# Radio_RPIv15_868.net
KiCad netlist of a schematic drawn in EAGLE
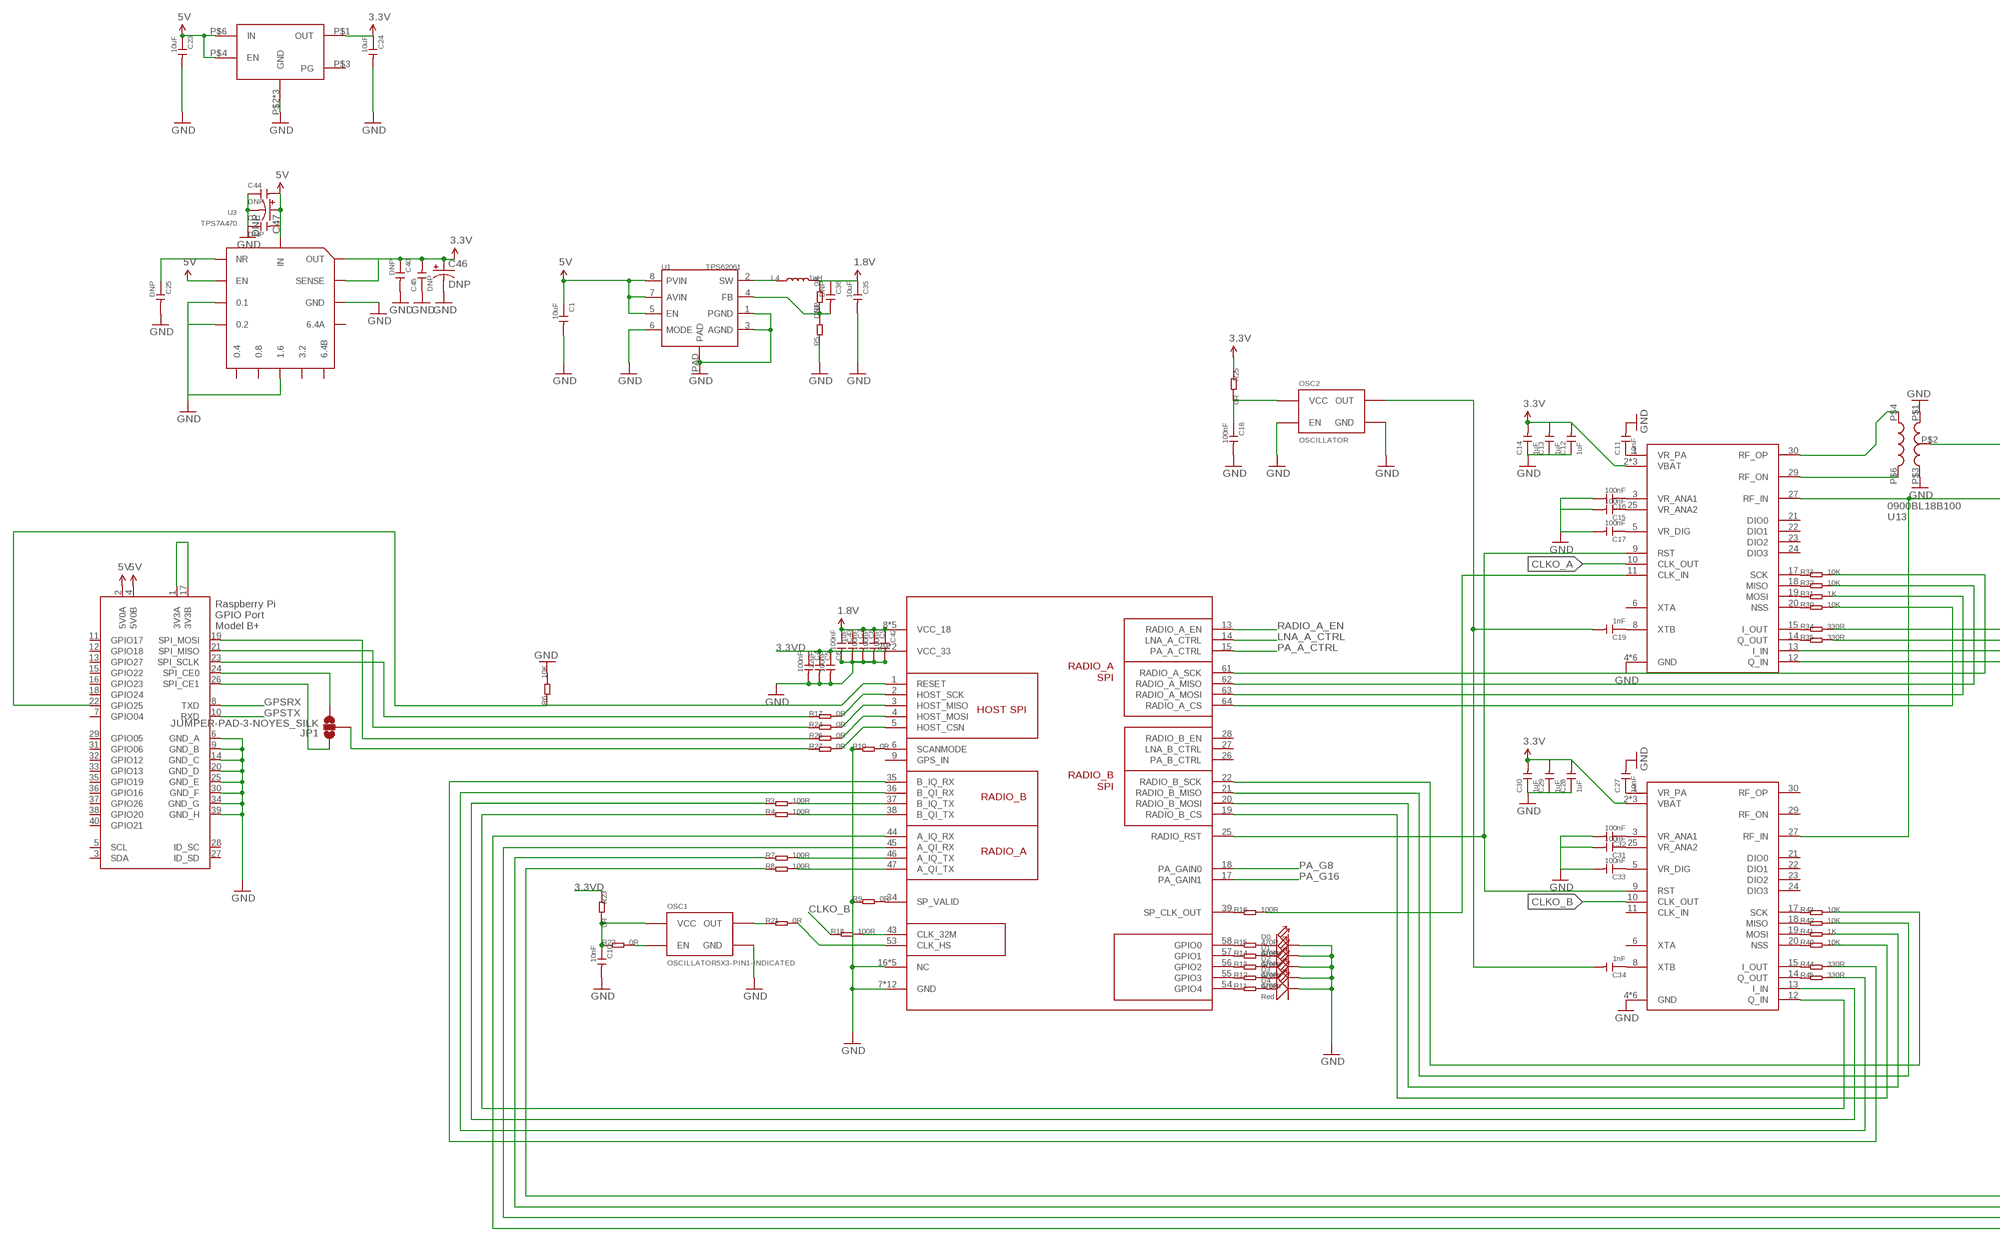
[diagram p0: schematic, sheet 1, part 1 of 2]
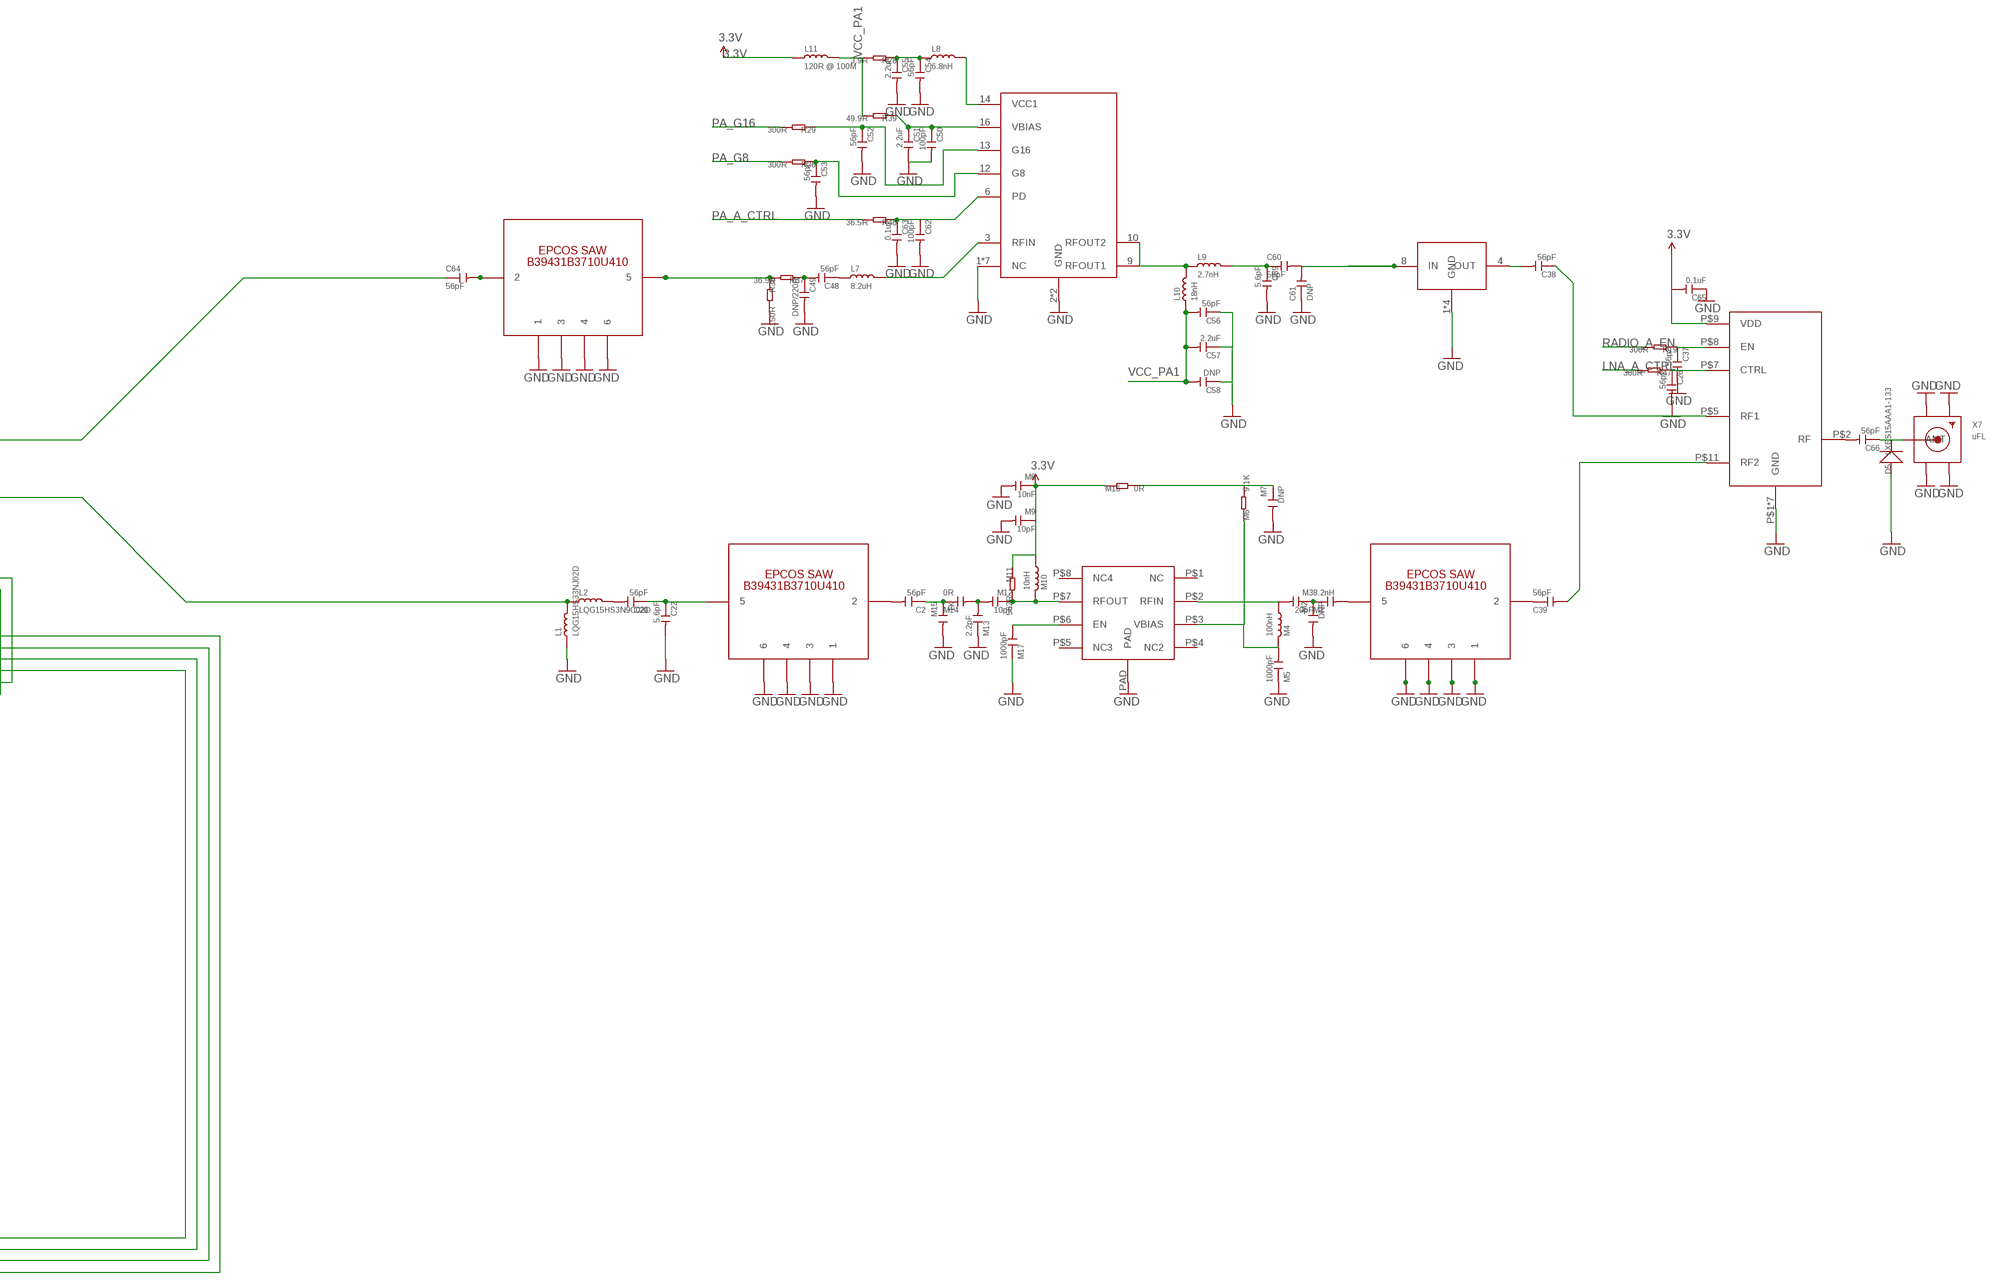
[diagram p1: schematic, sheet 1, part 2 of 2]

(export (version "E")
  (design (tool "Eeschema 10.0.6"))
  (components
    (comp (ref "C1")
      (value "10uF")
      (footprint "eagle-import:C0603@1")
      (libsource (lib "eagle-import") (part "CAP-0603"))
    )
    (comp (ref "C2")
      (value "56pF")
      (footprint "eagle-import:C0402@1")
      (libsource (lib "eagle-import") (part "CAP-0402"))
    )
    (comp (ref "C4")
      (value "100nF")
      (footprint "eagle-import:C0402@1")
      (libsource (lib "eagle-import") (part "CAP-0402"))
    )
    (comp (ref "C5")
      (value "22uF")
      (footprint "eagle-import:C0402@1")
      (libsource (lib "eagle-import") (part "CAP-0402"))
    )
    (comp (ref "C6")
      (value "100nF")
      (footprint "eagle-import:C0402@1")
      (libsource (lib "eagle-import") (part "CAP-0402"))
    )
    (comp (ref "C7")
      (value "1uF")
      (footprint "eagle-import:C0402@1")
      (libsource (lib "eagle-import") (part "CAP-0402"))
    )
    (comp (ref "C8")
      (value "100nF")
      (footprint "eagle-import:C0402@1")
      (libsource (lib "eagle-import") (part "CAP-0402"))
    )
    (comp (ref "C9")
      (value "100nF")
      (footprint "eagle-import:C0402@1")
      (libsource (lib "eagle-import") (part "CAP-0402"))
    )
    (comp (ref "C10")
      (value "10nF")
      (footprint "eagle-import:C0402@1")
      (libsource (lib "eagle-import") (part "CAP-0402"))
    )
    (comp (ref "C11")
      (value "10nF")
      (footprint "eagle-import:C0402@1")
      (libsource (lib "eagle-import") (part "CAP-0402"))
    )
    (comp (ref "C12")
      (value "1uF")
      (footprint "eagle-import:C0402@1")
      (libsource (lib "eagle-import") (part "CAP-0402"))
    )
    (comp (ref "C13")
      (value "1uF")
      (footprint "eagle-import:C0402@1")
      (libsource (lib "eagle-import") (part "CAP-0402"))
    )
    (comp (ref "C14")
      (value "1uF")
      (footprint "eagle-import:C0402@1")
      (libsource (lib "eagle-import") (part "CAP-0402"))
    )
    (comp (ref "C15")
      (value "100nF")
      (footprint "eagle-import:C0402@1")
      (libsource (lib "eagle-import") (part "CAP-0402"))
    )
    (comp (ref "C16")
      (value "100nF")
      (footprint "eagle-import:C0402@1")
      (libsource (lib "eagle-import") (part "CAP-0402"))
    )
    (comp (ref "C17")
      (value "100nF")
      (footprint "eagle-import:C0402@1")
      (libsource (lib "eagle-import") (part "CAP-0402"))
    )
    (comp (ref "C18")
      (value "100nF")
      (footprint "eagle-import:C0402@1")
      (libsource (lib "eagle-import") (part "CAP-0402"))
    )
    (comp (ref "C19")
      (value "1nF")
      (footprint "eagle-import:C0402@1")
      (libsource (lib "eagle-import") (part "CAP-0402"))
    )
    (comp (ref "C20")
      (value "56pF")
      (footprint "eagle-import:C0402@1")
      (libsource (lib "eagle-import") (part "CAP-0402"))
    )
    (comp (ref "C22")
      (value "5.6pF")
      (footprint "eagle-import:C0402@1")
      (libsource (lib "eagle-import") (part "CAP-0402"))
    )
    (comp (ref "C23")
      (value "10uF")
      (footprint "eagle-import:C0603@1")
      (libsource (lib "eagle-import") (part "CAP-0603"))
    )
    (comp (ref "C24")
      (value "10uF")
      (footprint "eagle-import:C0603@1")
      (libsource (lib "eagle-import") (part "CAP-0603"))
    )
    (comp (ref "C25")
      (value "DNP")
      (footprint "eagle-import:C0402@1")
      (libsource (lib "eagle-import") (part "CAP-0402"))
    )
    (comp (ref "C26")
      (value "56pF")
      (footprint "eagle-import:C0402@1")
      (libsource (lib "eagle-import") (part "CAP-0402"))
    )
    (comp (ref "C27")
      (value "10nF")
      (footprint "eagle-import:C0402@1")
      (libsource (lib "eagle-import") (part "CAP-0402"))
    )
    (comp (ref "C28")
      (value "1uF")
      (footprint "eagle-import:C0402@1")
      (libsource (lib "eagle-import") (part "CAP-0402"))
    )
    (comp (ref "C29")
      (value "1uF")
      (footprint "eagle-import:C0402@1")
      (libsource (lib "eagle-import") (part "CAP-0402"))
    )
    (comp (ref "C30")
      (value "1uF")
      (footprint "eagle-import:C0402@1")
      (libsource (lib "eagle-import") (part "CAP-0402"))
    )
    (comp (ref "C31")
      (value "100nF")
      (footprint "eagle-import:C0402@1")
      (libsource (lib "eagle-import") (part "CAP-0402"))
    )
    (comp (ref "C32")
      (value "100nF")
      (footprint "eagle-import:C0402@1")
      (libsource (lib "eagle-import") (part "CAP-0402"))
    )
    (comp (ref "C33")
      (value "100nF")
      (footprint "eagle-import:C0402@1")
      (libsource (lib "eagle-import") (part "CAP-0402"))
    )
    (comp (ref "C34")
      (value "1nF")
      (footprint "eagle-import:C0402@1")
      (libsource (lib "eagle-import") (part "CAP-0402"))
    )
    (comp (ref "C35")
      (value "10uF")
      (footprint "eagle-import:C0603@1")
      (libsource (lib "eagle-import") (part "CAP-0603"))
    )
    (comp (ref "C36")
      (value "DNP")
      (footprint "eagle-import:C0402@1")
      (libsource (lib "eagle-import") (part "CAP-0402"))
    )
    (comp (ref "C37")
      (value "56pF")
      (footprint "eagle-import:C0402@1")
      (libsource (lib "eagle-import") (part "CAP-0402"))
    )
    (comp (ref "C38")
      (value "56pF")
      (footprint "eagle-import:C0402@1")
      (libsource (lib "eagle-import") (part "CAP-0402"))
    )
    (comp (ref "C39")
      (value "56pF")
      (footprint "eagle-import:C0402@1")
      (libsource (lib "eagle-import") (part "CAP-0402"))
    )
    (comp (ref "C40")
      (value "DNP")
      (footprint "eagle-import:C0402@1")
      (libsource (lib "eagle-import") (part "CAP-0402"))
    )
    (comp (ref "C41")
      (value "DNP")
      (footprint "eagle-import:C0402@1")
      (libsource (lib "eagle-import") (part "CAP-0402"))
    )
    (comp (ref "C42")
      (value "100nF")
      (footprint "eagle-import:C0402@1")
      (libsource (lib "eagle-import") (part "CAP-0402"))
    )
    (comp (ref "C43")
      (value "100nF")
      (footprint "eagle-import:C0402@1")
      (libsource (lib "eagle-import") (part "CAP-0402"))
    )
    (comp (ref "C44")
      (value "DNP")
      (footprint "eagle-import:C0805@1")
      (libsource (lib "eagle-import") (part "CAP-0805"))
    )
    (comp (ref "C45")
      (value "DNP")
      (footprint "eagle-import:C0805@1")
      (libsource (lib "eagle-import") (part "CAP-0805"))
    )
    (comp (ref "C46")
      (value "DNP")
      (footprint "eagle-import:EIA3216")
      (libsource (lib "eagle-import") (part "CAP_POL1206"))
    )
    (comp (ref "C47")
      (value "DNP")
      (footprint "eagle-import:EIA3216")
      (libsource (lib "eagle-import") (part "CAP_POL1206"))
    )
    (comp (ref "C48")
      (value "56pF")
      (footprint "eagle-import:C0402@1")
      (libsource (lib "eagle-import") (part "CAP-0402"))
    )
    (comp (ref "C49")
      (value "DNP/220R")
      (footprint "eagle-import:C0402@1")
      (libsource (lib "eagle-import") (part "CAP-0402"))
    )
    (comp (ref "C50")
      (value "100pF")
      (footprint "eagle-import:C0402@1")
      (libsource (lib "eagle-import") (part "CAP-0402"))
    )
    (comp (ref "C51")
      (value "2.2uF")
      (footprint "eagle-import:C0402@1")
      (libsource (lib "eagle-import") (part "CAP-0402"))
    )
    (comp (ref "C52")
      (value "56pF")
      (footprint "eagle-import:C0402@1")
      (libsource (lib "eagle-import") (part "CAP-0402"))
    )
    (comp (ref "C53")
      (value "56pF")
      (footprint "eagle-import:C0402@1")
      (libsource (lib "eagle-import") (part "CAP-0402"))
    )
    (comp (ref "C54")
      (value "56pF")
      (footprint "eagle-import:C0402@1")
      (libsource (lib "eagle-import") (part "CAP-0402"))
    )
    (comp (ref "C55")
      (value "2.2uF")
      (footprint "eagle-import:C0402@1")
      (libsource (lib "eagle-import") (part "CAP-0402"))
    )
    (comp (ref "C56")
      (value "56pF")
      (footprint "eagle-import:C0402@1")
      (libsource (lib "eagle-import") (part "CAP-0402"))
    )
    (comp (ref "C57")
      (value "2.2uF")
      (footprint "eagle-import:C0402@1")
      (libsource (lib "eagle-import") (part "CAP-0402"))
    )
    (comp (ref "C58")
      (value "DNP")
      (footprint "eagle-import:C0402@1")
      (libsource (lib "eagle-import") (part "CAP-0402"))
    )
    (comp (ref "C59")
      (value "5.6pF")
      (footprint "eagle-import:C0402@1")
      (libsource (lib "eagle-import") (part "CAP-0402"))
    )
    (comp (ref "C60")
      (value "56pF")
      (footprint "eagle-import:C0402@1")
      (libsource (lib "eagle-import") (part "CAP-0402"))
    )
    (comp (ref "C61")
      (value "DNP")
      (footprint "eagle-import:C0402@1")
      (libsource (lib "eagle-import") (part "CAP-0402"))
    )
    (comp (ref "C62")
      (value "100pF")
      (footprint "eagle-import:C0402@1")
      (libsource (lib "eagle-import") (part "CAP-0402"))
    )
    (comp (ref "C63")
      (value "0.1uF")
      (footprint "eagle-import:C0402@1")
      (libsource (lib "eagle-import") (part "CAP-0402"))
    )
    (comp (ref "C64")
      (value "56pF")
      (footprint "eagle-import:C0402@1")
      (libsource (lib "eagle-import") (part "CAP-0402"))
    )
    (comp (ref "C65")
      (value "0.1uF")
      (footprint "eagle-import:C0402@1")
      (libsource (lib "eagle-import") (part "CAP-0402"))
    )
    (comp (ref "C66")
      (value "56pF")
      (footprint "eagle-import:C0402@1")
      (libsource (lib "eagle-import") (part "CAP-0402"))
    )
    (comp (ref "D0")
      (value "Green")
      (footprint "eagle-import:LED-0603")
      (libsource (lib "eagle-import") (part "LED-0603"))
    )
    (comp (ref "D1")
      (value "Green")
      (footprint "eagle-import:LED-0603")
      (libsource (lib "eagle-import") (part "LED-0603"))
    )
    (comp (ref "D2")
      (value "Green")
      (footprint "eagle-import:LED-0603")
      (libsource (lib "eagle-import") (part "LED-0603"))
    )
    (comp (ref "D3")
      (value "Green")
      (footprint "eagle-import:LED-0603")
      (libsource (lib "eagle-import") (part "LED-0603"))
    )
    (comp (ref "D4")
      (value "Red")
      (footprint "eagle-import:LED-0603")
      (libsource (lib "eagle-import") (part "LED-0603"))
    )
    (comp (ref "D5")
      (value "LXES15AAA1-133")
      (footprint "eagle-import:C0402")
      (libsource (lib "eagle-import") (part "D"))
    )
    (comp (ref "JP1")
      (value "JUMPER-PAD-3-NOYES_SILK")
      (footprint "eagle-import:PAD-JUMPER-3-NO_YES_SILK")
      (libsource (lib "eagle-import") (part "JUMPER-PAD-3-NOYES_SILK"))
    )
    (comp (ref "L1")
      (value "LQG15HS33NJ02D")
      (footprint "eagle-import:L0402@1")
      (libsource (lib "eagle-import") (part "INDUCTOR/FERRITE-BEAD-0402"))
    )
    (comp (ref "L2")
      (value "LQG15HS3N9C02D")
      (footprint "eagle-import:L0402@1")
      (libsource (lib "eagle-import") (part "INDUCTOR/FERRITE-BEAD-0402"))
    )
    (comp (ref "L4")
      (value "1uH")
      (footprint "eagle-import:1616BZ")
      (libsource (lib "eagle-import") (part "L'1616BZ'"))
    )
    (comp (ref "L7")
      (value "8.2uH")
      (footprint "eagle-import:L0402@1")
      (libsource (lib "eagle-import") (part "INDUCTOR/FERRITE-BEAD-0402"))
    )
    (comp (ref "L8")
      (value "6.8nH")
      (footprint "eagle-import:L0402@1")
      (libsource (lib "eagle-import") (part "INDUCTOR/FERRITE-BEAD-0402"))
    )
    (comp (ref "L9")
      (value "2.7nH")
      (footprint "eagle-import:L0402@1")
      (libsource (lib "eagle-import") (part "INDUCTOR/FERRITE-BEAD-0402"))
    )
    (comp (ref "L10")
      (value "18nH")
      (footprint "eagle-import:L0402@1")
      (libsource (lib "eagle-import") (part "INDUCTOR/FERRITE-BEAD-0402"))
    )
    (comp (ref "L11")
      (value "120R @ 100M")
      (footprint "eagle-import:L0402@1")
      (libsource (lib "eagle-import") (part "INDUCTOR/FERRITE-BEAD-0402"))
    )
    (comp (ref "M1")
      (value "8.2nH")
      (footprint "eagle-import:C0402@1")
      (libsource (lib "eagle-import") (part "CAP-0402"))
    )
    (comp (ref "M2")
      (value "DNP")
      (footprint "eagle-import:C0402@1")
      (libsource (lib "eagle-import") (part "CAP-0402"))
    )
    (comp (ref "M3")
      (value "20pF")
      (footprint "eagle-import:C0402@1")
      (libsource (lib "eagle-import") (part "CAP-0402"))
    )
    (comp (ref "M4")
      (value "100nH")
      (footprint "eagle-import:L0402@1")
      (libsource (lib "eagle-import") (part "INDUCTOR/FERRITE-BEAD-0402"))
    )
    (comp (ref "M5")
      (value "1000pF")
      (footprint "eagle-import:C0402@1")
      (libsource (lib "eagle-import") (part "CAP-0402"))
    )
    (comp (ref "M6")
      (value "9.1K")
      (footprint "eagle-import:R0402")
      (libsource (lib "eagle-import") (part "R-0402"))
    )
    (comp (ref "M7")
      (value "DNP")
      (footprint "eagle-import:C0402@1")
      (libsource (lib "eagle-import") (part "CAP-0402"))
    )
    (comp (ref "M8")
      (value "10nF")
      (footprint "eagle-import:C0402@1")
      (libsource (lib "eagle-import") (part "CAP-0402"))
    )
    (comp (ref "M9")
      (value "10pF")
      (footprint "eagle-import:C0402@1")
      (libsource (lib "eagle-import") (part "CAP-0402"))
    )
    (comp (ref "M10")
      (value "10nH")
      (footprint "eagle-import:L0402@1")
      (libsource (lib "eagle-import") (part "INDUCTOR/FERRITE-BEAD-0402"))
    )
    (comp (ref "M11")
      (value "562R")
      (footprint "eagle-import:R0402")
      (libsource (lib "eagle-import") (part "R-0402"))
    )
    (comp (ref "M12")
      (value "10pF")
      (footprint "eagle-import:C0402@1")
      (libsource (lib "eagle-import") (part "CAP-0402"))
    )
    (comp (ref "M13")
      (value "2.2pF")
      (footprint "eagle-import:C0402@1")
      (libsource (lib "eagle-import") (part "CAP-0402"))
    )
    (comp (ref "M14")
      (value "0R")
      (footprint "eagle-import:C0402@1")
      (libsource (lib "eagle-import") (part "CAP-0402"))
    )
    (comp (ref "M15")
      (value "1K")
      (footprint "eagle-import:C0402@1")
      (libsource (lib "eagle-import") (part "CAP-0402"))
    )
    (comp (ref "M16")
      (value "0R")
      (footprint "eagle-import:R0402")
      (libsource (lib "eagle-import") (part "R-0402"))
    )
    (comp (ref "M17")
      (value "1000pF")
      (footprint "eagle-import:C0402@1")
      (libsource (lib "eagle-import") (part "CAP-0402"))
    )
    (comp (ref "OSC1")
      (value "OSCILLATOR5X3-PIN1-INDICATED")
      (footprint "eagle-import:CRYSTAL-OSC-SMD-5X3")
      (libsource (lib "eagle-import") (part "OSCILLATOR5X3-PIN1-INDICATED"))
    )
    (comp (ref "OSC2")
      (value "OSCILLATOR")
      (footprint "eagle-import:CRYSTAL-OSC-SMD-3.2X2.5")
      (libsource (lib "eagle-import") (part "OSCILLATOR"))
    )
    (comp (ref "R1")
      (value "0R")
      (footprint "eagle-import:R0402")
      (libsource (lib "eagle-import") (part "R-0402"))
    )
    (comp (ref "R3")
      (value "100R")
      (footprint "eagle-import:R0402")
      (libsource (lib "eagle-import") (part "R-0402"))
    )
    (comp (ref "R4")
      (value "100R")
      (footprint "eagle-import:R0402")
      (libsource (lib "eagle-import") (part "R-0402"))
    )
    (comp (ref "R5")
      (value "DNP")
      (footprint "eagle-import:R0402")
      (libsource (lib "eagle-import") (part "R-0402"))
    )
    (comp (ref "R6")
      (value "10K")
      (footprint "eagle-import:R0402")
      (libsource (lib "eagle-import") (part "R-0402"))
    )
    (comp (ref "R7")
      (value "100R")
      (footprint "eagle-import:R0402")
      (libsource (lib "eagle-import") (part "R-0402"))
    )
    (comp (ref "R8")
      (value "100R")
      (footprint "eagle-import:R0402")
      (libsource (lib "eagle-import") (part "R-0402"))
    )
    (comp (ref "R9")
      (value "0R")
      (footprint "eagle-import:R0402")
      (libsource (lib "eagle-import") (part "R-0402"))
    )
    (comp (ref "R10")
      (value "0R")
      (footprint "eagle-import:R0402")
      (libsource (lib "eagle-import") (part "R-0402"))
    )
    (comp (ref "R11")
      (value "470R")
      (footprint "eagle-import:R0402")
      (libsource (lib "eagle-import") (part "R-0402"))
    )
    (comp (ref "R12")
      (value "470R")
      (footprint "eagle-import:R0402")
      (libsource (lib "eagle-import") (part "R-0402"))
    )
    (comp (ref "R13")
      (value "470R")
      (footprint "eagle-import:R0402")
      (libsource (lib "eagle-import") (part "R-0402"))
    )
    (comp (ref "R14")
      (value "470R")
      (footprint "eagle-import:R0402")
      (libsource (lib "eagle-import") (part "R-0402"))
    )
    (comp (ref "R15")
      (value "470R")
      (footprint "eagle-import:R0402")
      (libsource (lib "eagle-import") (part "R-0402"))
    )
    (comp (ref "R16")
      (value "100R")
      (footprint "eagle-import:R0402")
      (libsource (lib "eagle-import") (part "R-0402"))
    )
    (comp (ref "R17")
      (value "0R")
      (footprint "eagle-import:R0402")
      (libsource (lib "eagle-import") (part "R-0402"))
    )
    (comp (ref "R18")
      (value "100R")
      (footprint "eagle-import:R0402")
      (libsource (lib "eagle-import") (part "R-0402"))
    )
    (comp (ref "R19")
      (value "300R")
      (footprint "eagle-import:R0402")
      (libsource (lib "eagle-import") (part "R-0402"))
    )
    (comp (ref "R21")
      (value "0R")
      (footprint "eagle-import:R0402")
      (libsource (lib "eagle-import") (part "R-0402"))
    )
    (comp (ref "R22")
      (value "0R")
      (footprint "eagle-import:R0402")
      (libsource (lib "eagle-import") (part "R-0402"))
    )
    (comp (ref "R23")
      (value "0R")
      (footprint "eagle-import:R0402")
      (libsource (lib "eagle-import") (part "R-0402"))
    )
    (comp (ref "R24")
      (value "0R")
      (footprint "eagle-import:R0402")
      (libsource (lib "eagle-import") (part "R-0402"))
    )
    (comp (ref "R25")
      (value "0R")
      (footprint "eagle-import:R0402")
      (libsource (lib "eagle-import") (part "R-0402"))
    )
    (comp (ref "R26")
      (value "0R")
      (footprint "eagle-import:R0402")
      (libsource (lib "eagle-import") (part "R-0402"))
    )
    (comp (ref "R27")
      (value "0R")
      (footprint "eagle-import:R0402")
      (libsource (lib "eagle-import") (part "R-0402"))
    )
    (comp (ref "R28")
      (value "3.9R")
      (footprint "eagle-import:R0402")
      (libsource (lib "eagle-import") (part "R-0402"))
    )
    (comp (ref "R29")
      (value "300R")
      (footprint "eagle-import:R0402")
      (libsource (lib "eagle-import") (part "R-0402"))
    )
    (comp (ref "R30")
      (value "10K")
      (footprint "eagle-import:R0402")
      (libsource (lib "eagle-import") (part "R-0402"))
    )
    (comp (ref "R31")
      (value "1K")
      (footprint "eagle-import:R0402")
      (libsource (lib "eagle-import") (part "R-0402"))
    )
    (comp (ref "R32")
      (value "10K")
      (footprint "eagle-import:R0402")
      (libsource (lib "eagle-import") (part "R-0402"))
    )
    (comp (ref "R33")
      (value "10K")
      (footprint "eagle-import:R0402")
      (libsource (lib "eagle-import") (part "R-0402"))
    )
    (comp (ref "R34")
      (value "330R")
      (footprint "eagle-import:R0402")
      (libsource (lib "eagle-import") (part "R-0402"))
    )
    (comp (ref "R35")
      (value "330R")
      (footprint "eagle-import:R0402")
      (libsource (lib "eagle-import") (part "R-0402"))
    )
    (comp (ref "R36")
      (value "300R")
      (footprint "eagle-import:R0402")
      (libsource (lib "eagle-import") (part "R-0402"))
    )
    (comp (ref "R37")
      (value "36.5R")
      (footprint "eagle-import:R0402")
      (libsource (lib "eagle-import") (part "R-0402"))
    )
    (comp (ref "R38")
      (value "150R")
      (footprint "eagle-import:R0402")
      (libsource (lib "eagle-import") (part "R-0402"))
    )
    (comp (ref "R39")
      (value "49.9R")
      (footprint "eagle-import:R0402")
      (libsource (lib "eagle-import") (part "R-0402"))
    )
    (comp (ref "R40")
      (value "10K")
      (footprint "eagle-import:R0402")
      (libsource (lib "eagle-import") (part "R-0402"))
    )
    (comp (ref "R41")
      (value "1K")
      (footprint "eagle-import:R0402")
      (libsource (lib "eagle-import") (part "R-0402"))
    )
    (comp (ref "R42")
      (value "10K")
      (footprint "eagle-import:R0402")
      (libsource (lib "eagle-import") (part "R-0402"))
    )
    (comp (ref "R43")
      (value "10K")
      (footprint "eagle-import:R0402")
      (libsource (lib "eagle-import") (part "R-0402"))
    )
    (comp (ref "R44")
      (value "330R")
      (footprint "eagle-import:R0402")
      (libsource (lib "eagle-import") (part "R-0402"))
    )
    (comp (ref "R45")
      (value "330R")
      (footprint "eagle-import:R0402")
      (libsource (lib "eagle-import") (part "R-0402"))
    )
    (comp (ref "R46")
      (value "36.5R")
      (footprint "eagle-import:R0402")
      (libsource (lib "eagle-import") (part "R-0402"))
    )
    (comp (ref "R47")
      (value "300R")
      (footprint "eagle-import:R0402")
      (libsource (lib "eagle-import") (part "R-0402"))
    )
    (comp (ref "U$1")
      (value "SX1301")
      (footprint "eagle-import:QFN64G-0.5-9X9MM")
      (libsource (lib "eagle-import") (part "SX1301"))
    )
    (comp (ref "U$2")
      (value "SX1255")
      (footprint "eagle-import:QFN32G-0.5-5X5MM")
      (libsource (lib "eagle-import") (part "SX1255"))
    )
    (comp (ref "U$3")
      (value "SX1255")
      (footprint "eagle-import:QFN32G-0.5-5X5MM")
      (libsource (lib "eagle-import") (part "SX1255"))
    )
    (comp (ref "U$4")
      (value "B39921B3728U410")
      (footprint "eagle-import:EPCOS_SAW_FILTER")
      (libsource (lib "eagle-import") (part "EPCOS_SAW_FILTER"))
    )
    (comp (ref "U$5")
      (value "LP5912")
      (footprint "eagle-import:WSON6")
      (libsource (lib "eagle-import") (part "LP5912"))
    )
    (comp (ref "U$6")
      (value "0915LP15B026")
      (footprint "eagle-import:0915LP15B026")
      (libsource (lib "eagle-import") (part "0915LP15B026"))
    )
    (comp (ref "U$7")
      (value "RFSW1012")
      (footprint "eagle-import:QFN12-2X2MM")
      (libsource (lib "eagle-import") (part "RFSW1012"))
    )
    (comp (ref "U$8")
      (value "B39921B3728U410")
      (footprint "eagle-import:EPCOS_SAW_FILTER")
      (libsource (lib "eagle-import") (part "EPCOS_SAW_FILTER"))
    )
    (comp (ref "U$9")
      (value "EPCOS_SAW_FILTER")
      (footprint "eagle-import:EPCOS_SAW_FILTER")
      (libsource (lib "eagle-import") (part "EPCOS_SAW_FILTER"))
    )
    (comp (ref "U$10")
      (value "SKY67150_396LF")
      (footprint "eagle-import:8DFN")
      (libsource (lib "eagle-import") (part "SKY67150_396LF"))
    )
    (comp (ref "U1")
      (value "TPS62061")
      (footprint "eagle-import:WSON")
      (libsource (lib "eagle-import") (part "PMIC-ETA3410D2I-T(DFN8-2X2)WSON"))
    )
    (comp (ref "U3")
      (value "TPS7A470")
      (footprint "eagle-import:S-PVQFN-N20")
      (libsource (lib "eagle-import") (part "TPS7A470"))
    )
    (comp (ref "U6")
      (value "RFPA0133")
      (footprint "eagle-import:QFN16-3X3MM")
      (libsource (lib "eagle-import") (part "RFPA0133"))
    )
    (comp (ref "U13")
      (value "0900BL18B100")
      (footprint "eagle-import:BALUN_1206")
      (libsource (lib "eagle-import") (part "BALUN_1206"))
    )
    (comp (ref "X1")
      (value "RASPI_BOARD_B+#_H")
      (footprint "eagle-import:RASPI_BOARD_B+HAT")
      (libsource (lib "eagle-import") (part "RASPI_BOARD_B+#_H"))
    )
    (comp (ref "X7")
      (value "uFL")
      (footprint "eagle-import:SMA_EDGELAUNCH_UFL")
      (libsource (lib "eagle-import") (part "SMACONNECTOR_EDGE_UFL"))
    )
  )
  (nets
    (net (code "1") (name "/3.3VD") (class "Default")
      (node (ref "C4") (pin "1") (pinfunction "1_1") (pintype "passive"))
      (node (ref "C5") (pin "1") (pinfunction "1_1") (pintype "passive"))
      (node (ref "C6") (pin "1") (pinfunction "1_1") (pintype "passive"))
      (node (ref "R23") (pin "1") (pinfunction "1_1") (pintype "passive"))
      (node (ref "U$1") (pin "29") (pinfunction "VCC_33_29") (pintype "bidirectional"))
      (node (ref "U$1") (pin "52") (pinfunction "VCC_33_52") (pintype "bidirectional"))
    )
    (net (code "2") (name "/GPSRX") (class "Default")
      (node (ref "X1") (pin "8") (pinfunction "TXD_8") (pintype "bidirectional"))
    )
    (net (code "3") (name "/GPSTX") (class "Default")
      (node (ref "X1") (pin "10") (pinfunction "RXD_10") (pintype "bidirectional"))
    )
    (net (code "4") (name "/LNA_A_CTRL") (class "Default")
      (node (ref "R47") (pin "2") (pinfunction "2_2") (pintype "passive"))
      (node (ref "U$1") (pin "14") (pinfunction "LNA_A_CTRL_14") (pintype "bidirectional"))
    )
    (net (code "5") (name "/PA_A_CTRL") (class "Default")
      (node (ref "R46") (pin "2") (pinfunction "2_2") (pintype "passive"))
      (node (ref "U$1") (pin "15") (pinfunction "PA_A_CTRL_15") (pintype "bidirectional"))
    )
    (net (code "6") (name "/PA_G8") (class "Default")
      (node (ref "R36") (pin "2") (pinfunction "2_2") (pintype "passive"))
      (node (ref "U$1") (pin "18") (pinfunction "PA_GAIN0_18") (pintype "bidirectional"))
    )
    (net (code "7") (name "/PA_G16") (class "Default")
      (node (ref "R29") (pin "2") (pinfunction "2_2") (pintype "passive"))
      (node (ref "U$1") (pin "17") (pinfunction "PA_GAIN1_17") (pintype "bidirectional"))
    )
    (net (code "8") (name "/RADIO_A_EN") (class "Default")
      (node (ref "R19") (pin "2") (pinfunction "2_2") (pintype "passive"))
      (node (ref "U$1") (pin "13") (pinfunction "RADIO_A_EN_13") (pintype "bidirectional"))
    )
    (net (code "9") (name "/VCC_PA1") (class "Default")
      (node (ref "C56") (pin "2") (pinfunction "2_2") (pintype "passive"))
      (node (ref "C57") (pin "2") (pinfunction "2_2") (pintype "passive"))
      (node (ref "C58") (pin "2") (pinfunction "2_2") (pintype "passive"))
      (node (ref "L10") (pin "1") (pinfunction "1_1") (pintype "passive"))
      (node (ref "L11") (pin "2") (pinfunction "2_2") (pintype "passive"))
      (node (ref "R28") (pin "2") (pinfunction "2_2") (pintype "passive"))
      (node (ref "R39") (pin "2") (pinfunction "2_2") (pintype "passive"))
    )
    (net (code "10") (name "1.8V") (class "Default")
      (node (ref "C35") (pin "1") (pinfunction "1_1") (pintype "passive"))
      (node (ref "C36") (pin "1") (pinfunction "1_1") (pintype "passive"))
      (node (ref "C42") (pin "1") (pinfunction "1_1") (pintype "passive"))
      (node (ref "C43") (pin "1") (pinfunction "1_1") (pintype "passive"))
      (node (ref "C7") (pin "1") (pinfunction "1_1") (pintype "passive"))
      (node (ref "C8") (pin "1") (pinfunction "1_1") (pintype "passive"))
      (node (ref "C9") (pin "1") (pinfunction "1_1") (pintype "passive"))
      (node (ref "L4") (pin "2") (pinfunction "2_2") (pintype "passive"))
      (node (ref "R1") (pin "2") (pinfunction "2_2") (pintype "passive"))
      (node (ref "U$1") (pin "12") (pinfunction "VCC_18_12") (pintype "bidirectional"))
      (node (ref "U$1") (pin "23") (pinfunction "VCC_18_23") (pintype "bidirectional"))
      (node (ref "U$1") (pin "42") (pinfunction "VCC_18_42") (pintype "bidirectional"))
      (node (ref "U$1") (pin "60") (pinfunction "VCC_18_60") (pintype "bidirectional"))
      (node (ref "U$1") (pin "8") (pinfunction "VCC_18_8") (pintype "bidirectional"))
    )
    (net (code "11") (name "3.3V") (class "Default")
      (node (ref "C12") (pin "2") (pinfunction "2_2") (pintype "passive"))
      (node (ref "C13") (pin "2") (pinfunction "2_2") (pintype "passive"))
      (node (ref "C14") (pin "2") (pinfunction "2_2") (pintype "passive"))
      (node (ref "C24") (pin "1") (pinfunction "1_1") (pintype "passive"))
      (node (ref "C28") (pin "2") (pinfunction "2_2") (pintype "passive"))
      (node (ref "C29") (pin "2") (pinfunction "2_2") (pintype "passive"))
      (node (ref "C30") (pin "2") (pinfunction "2_2") (pintype "passive"))
      (node (ref "C40") (pin "1") (pinfunction "1_1") (pintype "passive"))
      (node (ref "C45") (pin "2") (pinfunction "2_2") (pintype "passive"))
      (node (ref "C46") (pin "A") (pinfunction "+_A") (pintype "passive"))
      (node (ref "C65") (pin "2") (pinfunction "2_2") (pintype "passive"))
      (node (ref "L11") (pin "1") (pinfunction "1_1") (pintype "passive"))
      (node (ref "M10") (pin "2") (pinfunction "2_2") (pintype "passive"))
      (node (ref "M11") (pin "1") (pinfunction "1_1") (pintype "passive"))
      (node (ref "M16") (pin "1") (pinfunction "1_1") (pintype "passive"))
      (node (ref "M8") (pin "1") (pinfunction "1_1") (pintype "passive"))
      (node (ref "M9") (pin "1") (pinfunction "1_1") (pintype "passive"))
      (node (ref "R25") (pin "1") (pinfunction "1_1") (pintype "passive"))
      (node (ref "U$2") (pin "16") (pinfunction "VBAT_16") (pintype "bidirectional"))
      (node (ref "U$2") (pin "2") (pinfunction "VBAT_2") (pintype "bidirectional"))
      (node (ref "U$2") (pin "32") (pinfunction "VBAT_32") (pintype "bidirectional"))
      (node (ref "U$3") (pin "16") (pinfunction "VBAT_16") (pintype "bidirectional"))
      (node (ref "U$3") (pin "2") (pinfunction "VBAT_2") (pintype "bidirectional"))
      (node (ref "U$3") (pin "32") (pinfunction "VBAT_32") (pintype "bidirectional"))
      (node (ref "U$5") (pin "P$1") (pinfunction "OUT_P$1") (pintype "bidirectional"))
      (node (ref "U$7") (pin "P$9") (pinfunction "VDD_P$9") (pintype "bidirectional"))
      (node (ref "U3") (pin "1") (pinfunction "OUT_1") (pintype "bidirectional"))
      (node (ref "U3") (pin "20") (pinfunction "OUT_20") (pintype "bidirectional"))
      (node (ref "U3") (pin "3") (pinfunction "SENSE_3") (pintype "bidirectional"))
    )
    (net (code "12") (name "5V") (class "Default")
      (node (ref "C1") (pin "1") (pinfunction "1_1") (pintype "passive"))
      (node (ref "C23") (pin "1") (pinfunction "1_1") (pintype "passive"))
      (node (ref "C41") (pin "2") (pinfunction "2_2") (pintype "passive"))
      (node (ref "C44") (pin "2") (pinfunction "2_2") (pintype "passive"))
      (node (ref "C47") (pin "A") (pinfunction "+_A") (pintype "passive"))
      (node (ref "U$5") (pin "P$4") (pinfunction "EN_P$4") (pintype "bidirectional"))
      (node (ref "U$5") (pin "P$6") (pinfunction "IN_P$6") (pintype "bidirectional"))
      (node (ref "U1") (pin "5") (pinfunction "EN_5") (pintype "bidirectional"))
      (node (ref "U1") (pin "7") (pinfunction "AVIN_7") (pintype "bidirectional"))
      (node (ref "U1") (pin "8") (pinfunction "PVIN_8") (pintype "bidirectional"))
      (node (ref "U3") (pin "13") (pinfunction "EN_13") (pintype "bidirectional"))
      (node (ref "U3") (pin "15") (pinfunction "IN_15") (pintype "bidirectional"))
      (node (ref "U3") (pin "16") (pinfunction "IN_16") (pintype "bidirectional"))
      (node (ref "X1") (pin "2") (pinfunction "5V0A_2") (pintype "power_in"))
      (node (ref "X1") (pin "4") (pinfunction "5V0B_4") (pintype "power_in"))
    )
    (net (code "13") (name "CLKO_A") (class "Default")
      (node (ref "U$2") (pin "10") (pinfunction "CLK_OUT_10") (pintype "bidirectional"))
    )
    (net (code "14") (name "CLKO_B") (class "Default")
      (node (ref "R18") (pin "1") (pinfunction "1_1") (pintype "passive"))
      (node (ref "U$3") (pin "10") (pinfunction "CLK_OUT_10") (pintype "bidirectional"))
    )
    (net (code "15") (name "GND") (class "Default")
      (node (ref "C1") (pin "2") (pinfunction "2_2") (pintype "passive"))
      (node (ref "C10") (pin "2") (pinfunction "2_2") (pintype "passive"))
      (node (ref "C11") (pin "2") (pinfunction "2_2") (pintype "passive"))
      (node (ref "C12") (pin "1") (pinfunction "1_1") (pintype "passive"))
      (node (ref "C13") (pin "1") (pinfunction "1_1") (pintype "passive"))
      (node (ref "C14") (pin "1") (pinfunction "1_1") (pintype "passive"))
      (node (ref "C15") (pin "2") (pinfunction "2_2") (pintype "passive"))
      (node (ref "C16") (pin "2") (pinfunction "2_2") (pintype "passive"))
      (node (ref "C17") (pin "2") (pinfunction "2_2") (pintype "passive"))
      (node (ref "C18") (pin "2") (pinfunction "2_2") (pintype "passive"))
      (node (ref "C22") (pin "2") (pinfunction "2_2") (pintype "passive"))
      (node (ref "C23") (pin "2") (pinfunction "2_2") (pintype "passive"))
      (node (ref "C24") (pin "2") (pinfunction "2_2") (pintype "passive"))
      (node (ref "C25") (pin "2") (pinfunction "2_2") (pintype "passive"))
      (node (ref "C26") (pin "2") (pinfunction "2_2") (pintype "passive"))
      (node (ref "C27") (pin "2") (pinfunction "2_2") (pintype "passive"))
      (node (ref "C28") (pin "1") (pinfunction "1_1") (pintype "passive"))
      (node (ref "C29") (pin "1") (pinfunction "1_1") (pintype "passive"))
      (node (ref "C30") (pin "1") (pinfunction "1_1") (pintype "passive"))
      (node (ref "C31") (pin "2") (pinfunction "2_2") (pintype "passive"))
      (node (ref "C32") (pin "2") (pinfunction "2_2") (pintype "passive"))
      (node (ref "C33") (pin "2") (pinfunction "2_2") (pintype "passive"))
      (node (ref "C35") (pin "2") (pinfunction "2_2") (pintype "passive"))
      (node (ref "C37") (pin "2") (pinfunction "2_2") (pintype "passive"))
      (node (ref "C4") (pin "2") (pinfunction "2_2") (pintype "passive"))
      (node (ref "C40") (pin "2") (pinfunction "2_2") (pintype "passive"))
      (node (ref "C41") (pin "1") (pinfunction "1_1") (pintype "passive"))
      (node (ref "C42") (pin "2") (pinfunction "2_2") (pintype "passive"))
      (node (ref "C43") (pin "2") (pinfunction "2_2") (pintype "passive"))
      (node (ref "C44") (pin "1") (pinfunction "1_1") (pintype "passive"))
      (node (ref "C45") (pin "1") (pinfunction "1_1") (pintype "passive"))
      (node (ref "C46") (pin "C") (pinfunction "-_C") (pintype "passive"))
      (node (ref "C47") (pin "C") (pinfunction "-_C") (pintype "passive"))
      (node (ref "C49") (pin "2") (pinfunction "2_2") (pintype "passive"))
      (node (ref "C5") (pin "2") (pinfunction "2_2") (pintype "passive"))
      (node (ref "C50") (pin "2") (pinfunction "2_2") (pintype "passive"))
      (node (ref "C51") (pin "2") (pinfunction "2_2") (pintype "passive"))
      (node (ref "C52") (pin "2") (pinfunction "2_2") (pintype "passive"))
      (node (ref "C53") (pin "2") (pinfunction "2_2") (pintype "passive"))
      (node (ref "C54") (pin "2") (pinfunction "2_2") (pintype "passive"))
      (node (ref "C55") (pin "2") (pinfunction "2_2") (pintype "passive"))
      (node (ref "C56") (pin "1") (pinfunction "1_1") (pintype "passive"))
      (node (ref "C57") (pin "1") (pinfunction "1_1") (pintype "passive"))
      (node (ref "C58") (pin "1") (pinfunction "1_1") (pintype "passive"))
      (node (ref "C59") (pin "2") (pinfunction "2_2") (pintype "passive"))
      (node (ref "C6") (pin "2") (pinfunction "2_2") (pintype "passive"))
      (node (ref "C61") (pin "1") (pinfunction "1_1") (pintype "passive"))
      (node (ref "C62") (pin "2") (pinfunction "2_2") (pintype "passive"))
      (node (ref "C63") (pin "2") (pinfunction "2_2") (pintype "passive"))
      (node (ref "C65") (pin "1") (pinfunction "1_1") (pintype "passive"))
      (node (ref "C7") (pin "2") (pinfunction "2_2") (pintype "passive"))
      (node (ref "C8") (pin "2") (pinfunction "2_2") (pintype "passive"))
      (node (ref "C9") (pin "2") (pinfunction "2_2") (pintype "passive"))
      (node (ref "D0") (pin "-") (pinfunction "-_-") (pintype "passive"))
      (node (ref "D1") (pin "-") (pinfunction "-_-") (pintype "passive"))
      (node (ref "D2") (pin "-") (pinfunction "-_-") (pintype "passive"))
      (node (ref "D3") (pin "-") (pinfunction "-_-") (pintype "passive"))
      (node (ref "D4") (pin "-") (pinfunction "-_-") (pintype "passive"))
      (node (ref "D5") (pin "1") (pinfunction "+_1") (pintype "passive"))
      (node (ref "L1") (pin "1") (pinfunction "1_1") (pintype "passive"))
      (node (ref "M13") (pin "1") (pinfunction "1_1") (pintype "passive"))
      (node (ref "M15") (pin "2") (pinfunction "2_2") (pintype "passive"))
      (node (ref "M17") (pin "1") (pinfunction "1_1") (pintype "passive"))
      (node (ref "M2") (pin "2") (pinfunction "2_2") (pintype "passive"))
      (node (ref "M5") (pin "1") (pinfunction "1_1") (pintype "passive"))
      (node (ref "M7") (pin "2") (pinfunction "2_2") (pintype "passive"))
      (node (ref "M8") (pin "2") (pinfunction "2_2") (pintype "passive"))
      (node (ref "M9") (pin "2") (pinfunction "2_2") (pintype "passive"))
      (node (ref "OSC1") (pin "2") (pinfunction "GND_2") (pintype "bidirectional"))
      (node (ref "OSC2") (pin "P$1") (pinfunction "EN_P$1") (pintype "bidirectional"))
      (node (ref "OSC2") (pin "P$2") (pinfunction "GND_P$2") (pintype "bidirectional"))
      (node (ref "R10") (pin "1") (pinfunction "1_1") (pintype "passive"))
      (node (ref "R38") (pin "2") (pinfunction "2_2") (pintype "passive"))
      (node (ref "R5") (pin "1") (pinfunction "1_1") (pintype "passive"))
      (node (ref "R6") (pin "2") (pinfunction "2_2") (pintype "passive"))
      (node (ref "R9") (pin "1") (pinfunction "1_1") (pintype "passive"))
      (node (ref "U$1") (pin "10") (pinfunction "GND_10") (pintype "bidirectional"))
      (node (ref "U$1") (pin "11") (pinfunction "GND_11") (pintype "bidirectional"))
      (node (ref "U$1") (pin "16") (pinfunction "NC_16") (pintype "bidirectional"))
      (node (ref "U$1") (pin "24") (pinfunction "GND_24") (pintype "bidirectional"))
      (node (ref "U$1") (pin "30") (pinfunction "GND_30") (pintype "bidirectional"))
      (node (ref "U$1") (pin "31") (pinfunction "GND_31") (pintype "bidirectional"))
      (node (ref "U$1") (pin "32") (pinfunction "NC_32") (pintype "bidirectional"))
      (node (ref "U$1") (pin "33") (pinfunction "NC_33") (pintype "bidirectional"))
      (node (ref "U$1") (pin "40") (pinfunction "GND_40") (pintype "bidirectional"))
      (node (ref "U$1") (pin "41") (pinfunction "GND_41") (pintype "bidirectional"))
      (node (ref "U$1") (pin "48") (pinfunction "NC_48") (pintype "bidirectional"))
      (node (ref "U$1") (pin "49") (pinfunction "NC_49") (pintype "bidirectional"))
      (node (ref "U$1") (pin "50") (pinfunction "GND_50") (pintype "bidirectional"))
      (node (ref "U$1") (pin "51") (pinfunction "GND_51") (pintype "bidirectional"))
      (node (ref "U$1") (pin "59") (pinfunction "GND_59") (pintype "bidirectional"))
      (node (ref "U$1") (pin "65") (pinfunction "GND_65") (pintype "bidirectional"))
      (node (ref "U$1") (pin "7") (pinfunction "GND_7") (pintype "bidirectional"))
      (node (ref "U$10") (pin "PAD") (pinfunction "PAD_PAD") (pintype "bidirectional"))
      (node (ref "U$2") (pin "26") (pinfunction "GND_26") (pintype "bidirectional"))
      (node (ref "U$2") (pin "28") (pinfunction "GND_28") (pintype "bidirectional"))
      (node (ref "U$2") (pin "31") (pinfunction "GND_31") (pintype "bidirectional"))
      (node (ref "U$2") (pin "33") (pinfunction "GND_33") (pintype "bidirectional"))
      (node (ref "U$2") (pin "4") (pinfunction "GND_4") (pintype "bidirectional"))
      (node (ref "U$2") (pin "7") (pinfunction "GND_7") (pintype "bidirectional"))
      (node (ref "U$3") (pin "26") (pinfunction "GND_26") (pintype "bidirectional"))
      (node (ref "U$3") (pin "28") (pinfunction "GND_28") (pintype "bidirectional"))
      (node (ref "U$3") (pin "31") (pinfunction "GND_31") (pintype "bidirectional"))
      (node (ref "U$3") (pin "33") (pinfunction "GND_33") (pintype "bidirectional"))
      (node (ref "U$3") (pin "4") (pinfunction "GND_4") (pintype "bidirectional"))
      (node (ref "U$3") (pin "7") (pinfunction "GND_7") (pintype "bidirectional"))
      (node (ref "U$4") (pin "P$1") (pinfunction "1_P$1") (pintype "bidirectional"))
      (node (ref "U$4") (pin "P$3") (pinfunction "3_P$3") (pintype "bidirectional"))
      (node (ref "U$4") (pin "P$4") (pinfunction "4_P$4") (pintype "bidirectional"))
      (node (ref "U$4") (pin "P$6") (pinfunction "6_P$6") (pintype "bidirectional"))
      (node (ref "U$5") (pin "P$2") (pinfunction "GND_P$2") (pintype "bidirectional"))
      (node (ref "U$5") (pin "P$5") (pinfunction "GND_P$5") (pintype "bidirectional"))
      (node (ref "U$5") (pin "PAD") (pinfunction "GND_PAD") (pintype "bidirectional"))
      (node (ref "U$6") (pin "1") (pinfunction "GND_1") (pintype "bidirectional"))
      (node (ref "U$6") (pin "3") (pinfunction "GND_3") (pintype "bidirectional"))
      (node (ref "U$6") (pin "5") (pinfunction "GND_5") (pintype "bidirectional"))
      (node (ref "U$6") (pin "7") (pinfunction "GND_7") (pintype "bidirectional"))
      (node (ref "U$7") (pin "P$1") (pinfunction "GND_P$1") (pintype "bidirectional"))
      (node (ref "U$7") (pin "P$10") (pinfunction "GND_P$10") (pintype "bidirectional"))
      (node (ref "U$7") (pin "P$12") (pinfunction "GND_P$12") (pintype "bidirectional"))
      (node (ref "U$7") (pin "P$3") (pinfunction "GND_P$3") (pintype "bidirectional"))
      (node (ref "U$7") (pin "P$4") (pinfunction "GND_P$4") (pintype "bidirectional"))
      (node (ref "U$7") (pin "P$6") (pinfunction "GND_P$6") (pintype "bidirectional"))
      (node (ref "U$7") (pin "PAD") (pinfunction "GND_PAD") (pintype "bidirectional"))
      (node (ref "U$8") (pin "P$1") (pinfunction "1_P$1") (pintype "bidirectional"))
      (node (ref "U$8") (pin "P$3") (pinfunction "3_P$3") (pintype "bidirectional"))
      (node (ref "U$8") (pin "P$4") (pinfunction "4_P$4") (pintype "bidirectional"))
      (node (ref "U$8") (pin "P$6") (pinfunction "6_P$6") (pintype "bidirectional"))
      (node (ref "U$9") (pin "P$1") (pinfunction "1_P$1") (pintype "bidirectional"))
      (node (ref "U$9") (pin "P$3") (pinfunction "3_P$3") (pintype "bidirectional"))
      (node (ref "U$9") (pin "P$4") (pinfunction "4_P$4") (pintype "bidirectional"))
      (node (ref "U$9") (pin "P$6") (pinfunction "6_P$6") (pintype "bidirectional"))
      (node (ref "U1") (pin "1") (pinfunction "PGND_1") (pintype "bidirectional"))
      (node (ref "U1") (pin "3") (pinfunction "AGND_3") (pintype "bidirectional"))
      (node (ref "U1") (pin "6") (pinfunction "MODE_6") (pintype "bidirectional"))
      (node (ref "U1") (pin "PAD") (pinfunction "PAD_PAD") (pintype "bidirectional"))
      (node (ref "U13") (pin "P$1") (pinfunction "GND_1_P$1") (pintype "bidirectional"))
      (node (ref "U13") (pin "P$3") (pinfunction "GND_2_P$3") (pintype "bidirectional"))
      (node (ref "U3") (pin "11") (pinfunction "0.2_11") (pintype "bidirectional"))
      (node (ref "U3") (pin "12") (pinfunction "0.1_12") (pintype "bidirectional"))
      (node (ref "U3") (pin "17") (pinfunction "GND_17") (pintype "bidirectional"))
      (node (ref "U3") (pin "18") (pinfunction "GND_18") (pintype "bidirectional"))
      (node (ref "U3") (pin "19") (pinfunction "GND_19") (pintype "bidirectional"))
      (node (ref "U3") (pin "2") (pinfunction "GND_2") (pintype "bidirectional"))
      (node (ref "U3") (pin "7") (pinfunction "GND_7") (pintype "bidirectional"))
      (node (ref "U3") (pin "8") (pinfunction "1.6_8") (pintype "bidirectional"))
      (node (ref "U3") (pin "EXP") (pinfunction "GND_EXP") (pintype "bidirectional"))
      (node (ref "U6") (pin "1") (pinfunction "NC_1") (pintype "bidirectional"))
      (node (ref "U6") (pin "11") (pinfunction "NC_11") (pintype "bidirectional"))
      (node (ref "U6") (pin "15") (pinfunction "NC_15") (pintype "bidirectional"))
      (node (ref "U6") (pin "2") (pinfunction "GND_2") (pintype "bidirectional"))
      (node (ref "U6") (pin "4") (pinfunction "NC_4") (pintype "bidirectional"))
      (node (ref "U6") (pin "5") (pinfunction "NC_5") (pintype "bidirectional"))
      (node (ref "U6") (pin "7") (pinfunction "NC_7") (pintype "bidirectional"))
      (node (ref "U6") (pin "8") (pinfunction "NC_8") (pintype "bidirectional"))
      (node (ref "U6") (pin "EXT") (pinfunction "GND_EXT") (pintype "bidirectional"))
      (node (ref "X1") (pin "14") (pinfunction "GND_C_14") (pintype "power_in"))
      (node (ref "X1") (pin "20") (pinfunction "GND_D_20") (pintype "power_in"))
      (node (ref "X1") (pin "25") (pinfunction "GND_E_25") (pintype "power_in"))
      (node (ref "X1") (pin "30") (pinfunction "GND_F_30") (pintype "power_in"))
      (node (ref "X1") (pin "34") (pinfunction "GND_G_34") (pintype "power_in"))
      (node (ref "X1") (pin "39") (pinfunction "GND_H_39") (pintype "power_in"))
      (node (ref "X1") (pin "6") (pinfunction "GND_A_6") (pintype "power_in"))
      (node (ref "X1") (pin "9") (pinfunction "GND_B_9") (pintype "power_in"))
      (node (ref "X7") (pin "GND@1") (pinfunction "GND1_GND@1") (pintype "power_in"))
      (node (ref "X7") (pin "GND@2") (pinfunction "GND2_GND@2") (pintype "power_in"))
      (node (ref "X7") (pin "GND@3") (pinfunction "GND3_GND@3") (pintype "power_in"))
      (node (ref "X7") (pin "GND@4") (pinfunction "GND4_GND@4") (pintype "power_in"))
    )
    (net (code "16") (name "Net-(C2-Pad1)") (class "Default")
      (node (ref "C2") (pin "1") (pinfunction "1_1") (pintype "passive"))
      (node (ref "M14") (pin "1") (pinfunction "1_1") (pintype "passive"))
      (node (ref "M15") (pin "1") (pinfunction "1_1") (pintype "passive"))
    )
    (net (code "17") (name "Net-(C20-Pad2)") (class "Default")
      (node (ref "C20") (pin "2") (pinfunction "2_2") (pintype "passive"))
      (node (ref "L2") (pin "2") (pinfunction "2_2") (pintype "passive"))
    )
    (net (code "18") (name "Net-(C48-Pad1)") (class "Default")
      (node (ref "C48") (pin "1") (pinfunction "1_1") (pintype "passive"))
      (node (ref "L7") (pin "1") (pinfunction "1_1") (pintype "passive"))
    )
    (net (code "19") (name "Net-(C48-Pad2)") (class "Default")
      (node (ref "C48") (pin "2") (pinfunction "2_2") (pintype "passive"))
      (node (ref "C49") (pin "1") (pinfunction "1_1") (pintype "passive"))
      (node (ref "R37") (pin "1") (pinfunction "1_1") (pintype "passive"))
    )
    (net (code "20") (name "Net-(C54-Pad1)") (class "Default")
      (node (ref "C54") (pin "1") (pinfunction "1_1") (pintype "passive"))
      (node (ref "C55") (pin "1") (pinfunction "1_1") (pintype "passive"))
      (node (ref "L8") (pin "1") (pinfunction "1_1") (pintype "passive"))
      (node (ref "R28") (pin "1") (pinfunction "1_1") (pintype "passive"))
    )
    (net (code "21") (name "Net-(C59-Pad1)") (class "Default")
      (node (ref "C59") (pin "1") (pinfunction "1_1") (pintype "passive"))
      (node (ref "C60") (pin "1") (pinfunction "1_1") (pintype "passive"))
      (node (ref "L9") (pin "2") (pinfunction "2_2") (pintype "passive"))
    )
    (net (code "22") (name "Net-(D0-Pad+)") (class "Default")
      (node (ref "D0") (pin "+") (pinfunction "+_+") (pintype "passive"))
      (node (ref "R15") (pin "2") (pinfunction "2_2") (pintype "passive"))
    )
    (net (code "23") (name "Net-(D1-Pad+)") (class "Default")
      (node (ref "D1") (pin "+") (pinfunction "+_+") (pintype "passive"))
      (node (ref "R14") (pin "2") (pinfunction "2_2") (pintype "passive"))
    )
    (net (code "24") (name "Net-(D2-Pad+)") (class "Default")
      (node (ref "D2") (pin "+") (pinfunction "+_+") (pintype "passive"))
      (node (ref "R13") (pin "2") (pinfunction "2_2") (pintype "passive"))
    )
    (net (code "25") (name "Net-(D3-Pad+)") (class "Default")
      (node (ref "D3") (pin "+") (pinfunction "+_+") (pintype "passive"))
      (node (ref "R12") (pin "2") (pinfunction "2_2") (pintype "passive"))
    )
    (net (code "26") (name "Net-(D4-Pad+)") (class "Default")
      (node (ref "D4") (pin "+") (pinfunction "+_+") (pintype "passive"))
      (node (ref "R11") (pin "2") (pinfunction "2_2") (pintype "passive"))
    )
    (net (code "27") (name "Net-(D5--)") (class "Default")
      (node (ref "C66") (pin "1") (pinfunction "1_1") (pintype "passive"))
      (node (ref "D5") (pin "2") (pinfunction "-_2") (pintype "passive"))
      (node (ref "X7") (pin "P") (pinfunction "ANT_P") (pintype "bidirectional"))
    )
    (net (code "28") (name "Net-(JP1-Pad2)") (class "Default")
      (node (ref "JP1") (pin "2") (pinfunction "2_2") (pintype "passive"))
      (node (ref "R27") (pin "1") (pinfunction "1_1") (pintype "passive"))
    )
    (net (code "29") (name "Net-(M1-Pad1)") (class "Default")
      (node (ref "M1") (pin "1") (pinfunction "1_1") (pintype "passive"))
      (node (ref "M2") (pin "1") (pinfunction "1_1") (pintype "passive"))
      (node (ref "M3") (pin "1") (pinfunction "1_1") (pintype "passive"))
    )
    (net (code "30") (name "Net-(M12-Pad2)") (class "Default")
      (node (ref "M12") (pin "2") (pinfunction "2_2") (pintype "passive"))
      (node (ref "M13") (pin "2") (pinfunction "2_2") (pintype "passive"))
      (node (ref "M14") (pin "2") (pinfunction "2_2") (pintype "passive"))
    )
    (net (code "31") (name "Net-(M16-Pad2)") (class "Default")
      (node (ref "M16") (pin "2") (pinfunction "2_2") (pintype "passive"))
      (node (ref "M6") (pin "2") (pinfunction "2_2") (pintype "passive"))
      (node (ref "M7") (pin "1") (pinfunction "1_1") (pintype "passive"))
    )
    (net (code "32") (name "Net-(OSC1-EN)") (class "Default")
      (node (ref "OSC1") (pin "1") (pinfunction "EN_1") (pintype "bidirectional"))
      (node (ref "R22") (pin "2") (pinfunction "2_2") (pintype "passive"))
    )
    (net (code "33") (name "Net-(OSC1-OUT)") (class "Default")
      (node (ref "OSC1") (pin "3") (pinfunction "OUT_3") (pintype "bidirectional"))
      (node (ref "R21") (pin "1") (pinfunction "1_1") (pintype "passive"))
    )
    (net (code "34") (name "Net-(OSC1-VCC)") (class "Default")
      (node (ref "C10") (pin "1") (pinfunction "1_1") (pintype "passive"))
      (node (ref "OSC1") (pin "4") (pinfunction "VCC_4") (pintype "bidirectional"))
      (node (ref "R22") (pin "1") (pinfunction "1_1") (pintype "passive"))
      (node (ref "R23") (pin "2") (pinfunction "2_2") (pintype "passive"))
    )
    (net (code "35") (name "Net-(OSC2-OUT)") (class "Default")
      (node (ref "C19") (pin "2") (pinfunction "2_2") (pintype "passive"))
      (node (ref "C34") (pin "2") (pinfunction "2_2") (pintype "passive"))
      (node (ref "OSC2") (pin "P$3") (pinfunction "OUT_P$3") (pintype "bidirectional"))
    )
    (net (code "36") (name "Net-(OSC2-VCC)") (class "Default")
      (node (ref "C18") (pin "1") (pinfunction "1_1") (pintype "passive"))
      (node (ref "OSC2") (pin "P$4") (pinfunction "VCC_P$4") (pintype "bidirectional"))
      (node (ref "R25") (pin "2") (pinfunction "2_2") (pintype "passive"))
    )
    (net (code "37") (name "Net-(U$1-A_IQ_RX)") (class "Default")
      (node (ref "R34") (pin "2") (pinfunction "2_2") (pintype "passive"))
      (node (ref "U$1") (pin "44") (pinfunction "A_IQ_RX_44") (pintype "bidirectional"))
    )
    (net (code "38") (name "Net-(U$1-A_IQ_TX)") (class "Default")
      (node (ref "R7") (pin "2") (pinfunction "2_2") (pintype "passive"))
      (node (ref "U$1") (pin "46") (pinfunction "A_IQ_TX_46") (pintype "bidirectional"))
    )
    (net (code "39") (name "Net-(U$1-A_QI_RX)") (class "Default")
      (node (ref "R35") (pin "2") (pinfunction "2_2") (pintype "passive"))
      (node (ref "U$1") (pin "45") (pinfunction "A_QI_RX_45") (pintype "bidirectional"))
    )
    (net (code "40") (name "Net-(U$1-A_QI_TX)") (class "Default")
      (node (ref "R8") (pin "2") (pinfunction "2_2") (pintype "passive"))
      (node (ref "U$1") (pin "47") (pinfunction "A_QI_TX_47") (pintype "bidirectional"))
    )
    (net (code "41") (name "Net-(U$1-B_IQ_RX)") (class "Default")
      (node (ref "R44") (pin "2") (pinfunction "2_2") (pintype "passive"))
      (node (ref "U$1") (pin "35") (pinfunction "B_IQ_RX_35") (pintype "bidirectional"))
    )
    (net (code "42") (name "Net-(U$1-B_IQ_TX)") (class "Default")
      (node (ref "R3") (pin "2") (pinfunction "2_2") (pintype "passive"))
      (node (ref "U$1") (pin "37") (pinfunction "B_IQ_TX_37") (pintype "bidirectional"))
    )
    (net (code "43") (name "Net-(U$1-B_QI_RX)") (class "Default")
      (node (ref "R45") (pin "2") (pinfunction "2_2") (pintype "passive"))
      (node (ref "U$1") (pin "36") (pinfunction "B_QI_RX_36") (pintype "bidirectional"))
    )
    (net (code "44") (name "Net-(U$1-B_QI_TX)") (class "Default")
      (node (ref "R4") (pin "2") (pinfunction "2_2") (pintype "passive"))
      (node (ref "U$1") (pin "38") (pinfunction "B_QI_TX_38") (pintype "bidirectional"))
    )
    (net (code "45") (name "Net-(U$1-CLK_32M)") (class "Default")
      (node (ref "R18") (pin "2") (pinfunction "2_2") (pintype "passive"))
      (node (ref "U$1") (pin "43") (pinfunction "CLK_32M_43") (pintype "bidirectional"))
    )
    (net (code "46") (name "Net-(U$1-CLK_HS)") (class "Default")
      (node (ref "R21") (pin "2") (pinfunction "2_2") (pintype "passive"))
      (node (ref "U$1") (pin "53") (pinfunction "CLK_HS_53") (pintype "bidirectional"))
    )
    (net (code "47") (name "Net-(U$1-GPIO0)") (class "Default")
      (node (ref "R15") (pin "1") (pinfunction "1_1") (pintype "passive"))
      (node (ref "U$1") (pin "58") (pinfunction "GPIO0_58") (pintype "bidirectional"))
    )
    (net (code "48") (name "Net-(U$1-GPIO1)") (class "Default")
      (node (ref "R14") (pin "1") (pinfunction "1_1") (pintype "passive"))
      (node (ref "U$1") (pin "57") (pinfunction "GPIO1_57") (pintype "bidirectional"))
    )
    (net (code "49") (name "Net-(U$1-GPIO2)") (class "Default")
      (node (ref "R13") (pin "1") (pinfunction "1_1") (pintype "passive"))
      (node (ref "U$1") (pin "56") (pinfunction "GPIO2_56") (pintype "bidirectional"))
    )
    (net (code "50") (name "Net-(U$1-GPIO3)") (class "Default")
      (node (ref "R12") (pin "1") (pinfunction "1_1") (pintype "passive"))
      (node (ref "U$1") (pin "55") (pinfunction "GPIO3_55") (pintype "bidirectional"))
    )
    (net (code "51") (name "Net-(U$1-GPIO4)") (class "Default")
      (node (ref "R11") (pin "1") (pinfunction "1_1") (pintype "passive"))
      (node (ref "U$1") (pin "54") (pinfunction "GPIO4_54") (pintype "bidirectional"))
    )
    (net (code "52") (name "Net-(U$1-HOST_CSN)") (class "Default")
      (node (ref "R27") (pin "2") (pinfunction "2_2") (pintype "passive"))
      (node (ref "U$1") (pin "5") (pinfunction "HOST_CSN_5") (pintype "bidirectional"))
    )
    (net (code "53") (name "Net-(U$1-HOST_MISO)") (class "Default")
      (node (ref "R24") (pin "2") (pinfunction "2_2") (pintype "passive"))
      (node (ref "U$1") (pin "3") (pinfunction "HOST_MISO_3") (pintype "bidirectional"))
    )
    (net (code "54") (name "Net-(U$1-HOST_MOSI)") (class "Default")
      (node (ref "R26") (pin "2") (pinfunction "2_2") (pintype "passive"))
      (node (ref "U$1") (pin "4") (pinfunction "HOST_MOSI_4") (pintype "bidirectional"))
    )
    (net (code "55") (name "Net-(U$1-HOST_SCK)") (class "Default")
      (node (ref "R17") (pin "2") (pinfunction "2_2") (pintype "passive"))
      (node (ref "U$1") (pin "2") (pinfunction "HOST_SCK_2") (pintype "bidirectional"))
    )
    (net (code "56") (name "Net-(U$1-RADIO_A_CS)") (class "Default")
      (node (ref "R30") (pin "2") (pinfunction "2_2") (pintype "passive"))
      (node (ref "U$1") (pin "64") (pinfunction "RADIO_A_CS_64") (pintype "bidirectional"))
    )
    (net (code "57") (name "Net-(U$1-RADIO_A_MISO)") (class "Default")
      (node (ref "R32") (pin "2") (pinfunction "2_2") (pintype "passive"))
      (node (ref "U$1") (pin "62") (pinfunction "RADIO_A_MISO_62") (pintype "bidirectional"))
    )
    (net (code "58") (name "Net-(U$1-RADIO_A_MOSI)") (class "Default")
      (node (ref "R31") (pin "2") (pinfunction "2_2") (pintype "passive"))
      (node (ref "U$1") (pin "63") (pinfunction "RADIO_A_MOSI_63") (pintype "bidirectional"))
    )
    (net (code "59") (name "Net-(U$1-RADIO_A_SCK)") (class "Default")
      (node (ref "R33") (pin "2") (pinfunction "2_2") (pintype "passive"))
      (node (ref "U$1") (pin "61") (pinfunction "RADIO_A_SCK_61") (pintype "bidirectional"))
    )
    (net (code "60") (name "Net-(U$1-RADIO_B_CS)") (class "Default")
      (node (ref "R40") (pin "2") (pinfunction "2_2") (pintype "passive"))
      (node (ref "U$1") (pin "19") (pinfunction "RADIO_B_CS_19") (pintype "bidirectional"))
    )
    (net (code "61") (name "Net-(U$1-RADIO_B_MISO)") (class "Default")
      (node (ref "R42") (pin "2") (pinfunction "2_2") (pintype "passive"))
      (node (ref "U$1") (pin "21") (pinfunction "RADIO_B_MISO_21") (pintype "bidirectional"))
    )
    (net (code "62") (name "Net-(U$1-RADIO_B_MOSI)") (class "Default")
      (node (ref "R41") (pin "2") (pinfunction "2_2") (pintype "passive"))
      (node (ref "U$1") (pin "20") (pinfunction "RADIO_B_MOSI_20") (pintype "bidirectional"))
    )
    (net (code "63") (name "Net-(U$1-RADIO_B_SCK)") (class "Default")
      (node (ref "R43") (pin "2") (pinfunction "2_2") (pintype "passive"))
      (node (ref "U$1") (pin "22") (pinfunction "RADIO_B_SCK_22") (pintype "bidirectional"))
    )
    (net (code "64") (name "Net-(U$1-RADIO_RST)") (class "Default")
      (node (ref "U$1") (pin "25") (pinfunction "RADIO_RST_25") (pintype "bidirectional"))
      (node (ref "U$2") (pin "9") (pinfunction "RST_9") (pintype "bidirectional"))
      (node (ref "U$3") (pin "9") (pinfunction "RST_9") (pintype "bidirectional"))
    )
    (net (code "65") (name "Net-(U$1-RESET)") (class "Default")
      (node (ref "R6") (pin "1") (pinfunction "1_1") (pintype "passive"))
      (node (ref "U$1") (pin "1") (pinfunction "RESET_1") (pintype "bidirectional"))
      (node (ref "X1") (pin "22") (pinfunction "GPIO25_22") (pintype "bidirectional"))
    )
    (net (code "66") (name "Net-(U$1-SCANMODE)") (class "Default")
      (node (ref "R10") (pin "2") (pinfunction "2_2") (pintype "passive"))
      (node (ref "U$1") (pin "6") (pinfunction "SCANMODE_6") (pintype "bidirectional"))
    )
    (net (code "67") (name "Net-(U$1-SP_CLK_OUT)") (class "Default")
      (node (ref "R16") (pin "1") (pinfunction "1_1") (pintype "passive"))
      (node (ref "U$1") (pin "39") (pinfunction "SP_CLK_OUT_39") (pintype "bidirectional"))
    )
    (net (code "68") (name "Net-(U$1-SP_VALID)") (class "Default")
      (node (ref "R9") (pin "2") (pinfunction "2_2") (pintype "passive"))
      (node (ref "U$1") (pin "34") (pinfunction "SP_VALID_34") (pintype "bidirectional"))
    )
    (net (code "69") (name "Net-(U$2-CLK_IN)") (class "Default")
      (node (ref "R16") (pin "2") (pinfunction "2_2") (pintype "passive"))
      (node (ref "U$2") (pin "11") (pinfunction "CLK_IN_11") (pintype "bidirectional"))
    )
    (net (code "70") (name "Net-(U$2-I_IN)") (class "Default")
      (node (ref "R7") (pin "1") (pinfunction "1_1") (pintype "passive"))
      (node (ref "U$2") (pin "13") (pinfunction "I_IN_13") (pintype "bidirectional"))
    )
    (net (code "71") (name "Net-(U$2-I_OUT)") (class "Default")
      (node (ref "R34") (pin "1") (pinfunction "1_1") (pintype "passive"))
      (node (ref "U$2") (pin "15") (pinfunction "I_OUT_15") (pintype "bidirectional"))
    )
    (net (code "72") (name "Net-(U$2-MISO)") (class "Default")
      (node (ref "R32") (pin "1") (pinfunction "1_1") (pintype "passive"))
      (node (ref "U$2") (pin "18") (pinfunction "MISO_18") (pintype "bidirectional"))
    )
    (net (code "73") (name "Net-(U$2-MOSI)") (class "Default")
      (node (ref "R31") (pin "1") (pinfunction "1_1") (pintype "passive"))
      (node (ref "U$2") (pin "19") (pinfunction "MOSI_19") (pintype "bidirectional"))
    )
    (net (code "74") (name "Net-(U$2-NSS)") (class "Default")
      (node (ref "R30") (pin "1") (pinfunction "1_1") (pintype "passive"))
      (node (ref "U$2") (pin "20") (pinfunction "NSS_20") (pintype "bidirectional"))
    )
    (net (code "75") (name "Net-(U$2-Q_IN)") (class "Default")
      (node (ref "R8") (pin "1") (pinfunction "1_1") (pintype "passive"))
      (node (ref "U$2") (pin "12") (pinfunction "Q_IN_12") (pintype "bidirectional"))
    )
    (net (code "76") (name "Net-(U$2-Q_OUT)") (class "Default")
      (node (ref "R35") (pin "1") (pinfunction "1_1") (pintype "passive"))
      (node (ref "U$2") (pin "14") (pinfunction "Q_OUT_14") (pintype "bidirectional"))
    )
    (net (code "77") (name "Net-(U$2-RF_IN)") (class "Default")
      (node (ref "L1") (pin "2") (pinfunction "2_2") (pintype "passive"))
      (node (ref "L2") (pin "1") (pinfunction "1_1") (pintype "passive"))
      (node (ref "U$2") (pin "27") (pinfunction "RF_IN_27") (pintype "bidirectional"))
      (node (ref "U$3") (pin "27") (pinfunction "RF_IN_27") (pintype "bidirectional"))
    )
    (net (code "78") (name "Net-(U$2-RF_ON)") (class "Default")
      (node (ref "U$2") (pin "29") (pinfunction "RF_ON_29") (pintype "bidirectional"))
      (node (ref "U13") (pin "P$6") (pinfunction "BALANCE_2_P$6") (pintype "bidirectional"))
    )
    (net (code "79") (name "Net-(U$2-RF_OP)") (class "Default")
      (node (ref "U$2") (pin "30") (pinfunction "RF_OP_30") (pintype "bidirectional"))
      (node (ref "U13") (pin "P$4") (pinfunction "BALANCE_1_P$4") (pintype "bidirectional"))
    )
    (net (code "80") (name "Net-(U$2-SCK)") (class "Default")
      (node (ref "R33") (pin "1") (pinfunction "1_1") (pintype "passive"))
      (node (ref "U$2") (pin "17") (pinfunction "SCK_17") (pintype "bidirectional"))
    )
    (net (code "81") (name "Net-(U$2-VR_ANA1)") (class "Default")
      (node (ref "C16") (pin "1") (pinfunction "1_1") (pintype "passive"))
      (node (ref "U$2") (pin "3") (pinfunction "VR_ANA1_3") (pintype "bidirectional"))
    )
    (net (code "82") (name "Net-(U$2-VR_ANA2)") (class "Default")
      (node (ref "C15") (pin "1") (pinfunction "1_1") (pintype "passive"))
      (node (ref "U$2") (pin "25") (pinfunction "VR_ANA2_25") (pintype "bidirectional"))
    )
    (net (code "83") (name "Net-(U$2-VR_DIG)") (class "Default")
      (node (ref "C17") (pin "1") (pinfunction "1_1") (pintype "passive"))
      (node (ref "U$2") (pin "5") (pinfunction "VR_DIG_5") (pintype "bidirectional"))
    )
    (net (code "84") (name "Net-(U$2-VR_PA)") (class "Default")
      (node (ref "C11") (pin "1") (pinfunction "1_1") (pintype "passive"))
      (node (ref "U$2") (pin "1") (pinfunction "VR_PA_1") (pintype "bidirectional"))
    )
    (net (code "85") (name "Net-(U$2-XTB)") (class "Default")
      (node (ref "C19") (pin "1") (pinfunction "1_1") (pintype "passive"))
      (node (ref "U$2") (pin "8") (pinfunction "XTB_8") (pintype "bidirectional"))
    )
    (net (code "86") (name "Net-(U$3-I_IN)") (class "Default")
      (node (ref "R3") (pin "1") (pinfunction "1_1") (pintype "passive"))
      (node (ref "U$3") (pin "13") (pinfunction "I_IN_13") (pintype "bidirectional"))
    )
    (net (code "87") (name "Net-(U$3-I_OUT)") (class "Default")
      (node (ref "R44") (pin "1") (pinfunction "1_1") (pintype "passive"))
      (node (ref "U$3") (pin "15") (pinfunction "I_OUT_15") (pintype "bidirectional"))
    )
    (net (code "88") (name "Net-(U$3-MISO)") (class "Default")
      (node (ref "R42") (pin "1") (pinfunction "1_1") (pintype "passive"))
      (node (ref "U$3") (pin "18") (pinfunction "MISO_18") (pintype "bidirectional"))
    )
    (net (code "89") (name "Net-(U$3-MOSI)") (class "Default")
      (node (ref "R41") (pin "1") (pinfunction "1_1") (pintype "passive"))
      (node (ref "U$3") (pin "19") (pinfunction "MOSI_19") (pintype "bidirectional"))
    )
    (net (code "90") (name "Net-(U$3-NSS)") (class "Default")
      (node (ref "R40") (pin "1") (pinfunction "1_1") (pintype "passive"))
      (node (ref "U$3") (pin "20") (pinfunction "NSS_20") (pintype "bidirectional"))
    )
    (net (code "91") (name "Net-(U$3-Q_IN)") (class "Default")
      (node (ref "R4") (pin "1") (pinfunction "1_1") (pintype "passive"))
      (node (ref "U$3") (pin "12") (pinfunction "Q_IN_12") (pintype "bidirectional"))
    )
    (net (code "92") (name "Net-(U$3-Q_OUT)") (class "Default")
      (node (ref "R45") (pin "1") (pinfunction "1_1") (pintype "passive"))
      (node (ref "U$3") (pin "14") (pinfunction "Q_OUT_14") (pintype "bidirectional"))
    )
    (net (code "93") (name "Net-(U$3-SCK)") (class "Default")
      (node (ref "R43") (pin "1") (pinfunction "1_1") (pintype "passive"))
      (node (ref "U$3") (pin "17") (pinfunction "SCK_17") (pintype "bidirectional"))
    )
    (net (code "94") (name "Net-(U$3-VR_ANA1)") (class "Default")
      (node (ref "C32") (pin "1") (pinfunction "1_1") (pintype "passive"))
      (node (ref "U$3") (pin "3") (pinfunction "VR_ANA1_3") (pintype "bidirectional"))
    )
    (net (code "95") (name "Net-(U$3-VR_ANA2)") (class "Default")
      (node (ref "C31") (pin "1") (pinfunction "1_1") (pintype "passive"))
      (node (ref "U$3") (pin "25") (pinfunction "VR_ANA2_25") (pintype "bidirectional"))
    )
    (net (code "96") (name "Net-(U$3-VR_DIG)") (class "Default")
      (node (ref "C33") (pin "1") (pinfunction "1_1") (pintype "passive"))
      (node (ref "U$3") (pin "5") (pinfunction "VR_DIG_5") (pintype "bidirectional"))
    )
    (net (code "97") (name "Net-(U$3-VR_PA)") (class "Default")
      (node (ref "C27") (pin "1") (pinfunction "1_1") (pintype "passive"))
      (node (ref "U$3") (pin "1") (pinfunction "VR_PA_1") (pintype "bidirectional"))
    )
    (net (code "98") (name "Net-(U$3-XTB)") (class "Default")
      (node (ref "C34") (pin "1") (pinfunction "1_1") (pintype "passive"))
      (node (ref "U$3") (pin "8") (pinfunction "XTB_8") (pintype "bidirectional"))
    )
    (net (code "99") (name "Net-(U$4-2)") (class "Default")
      (node (ref "C2") (pin "2") (pinfunction "2_2") (pintype "passive"))
      (node (ref "U$4") (pin "P$2") (pinfunction "2_P$2") (pintype "bidirectional"))
    )
    (net (code "100") (name "Net-(U$4-5)") (class "Default")
      (node (ref "C20") (pin "1") (pinfunction "1_1") (pintype "passive"))
      (node (ref "C22") (pin "1") (pinfunction "1_1") (pintype "passive"))
      (node (ref "U$4") (pin "P$5") (pinfunction "5_P$5") (pintype "bidirectional"))
    )
    (net (code "101") (name "Net-(U$6-IN)") (class "Default")
      (node (ref "C60") (pin "2") (pinfunction "2_2") (pintype "passive"))
      (node (ref "C61") (pin "2") (pinfunction "2_2") (pintype "passive"))
      (node (ref "U$6") (pin "8") (pinfunction "IN_8") (pintype "bidirectional"))
    )
    (net (code "102") (name "Net-(U$6-OUT)") (class "Default")
      (node (ref "C38") (pin "2") (pinfunction "2_2") (pintype "passive"))
      (node (ref "U$6") (pin "4") (pinfunction "OUT_4") (pintype "bidirectional"))
    )
    (net (code "103") (name "Net-(U$7-CTRL)") (class "Default")
      (node (ref "C26") (pin "1") (pinfunction "1_1") (pintype "passive"))
      (node (ref "R47") (pin "1") (pinfunction "1_1") (pintype "passive"))
      (node (ref "U$7") (pin "P$7") (pinfunction "CTRL_P$7") (pintype "bidirectional"))
    )
    (net (code "104") (name "Net-(U$7-EN)") (class "Default")
      (node (ref "C37") (pin "1") (pinfunction "1_1") (pintype "passive"))
      (node (ref "R19") (pin "1") (pinfunction "1_1") (pintype "passive"))
      (node (ref "U$7") (pin "P$8") (pinfunction "EN_P$8") (pintype "bidirectional"))
    )
    (net (code "105") (name "Net-(U$7-RF)") (class "Default")
      (node (ref "C66") (pin "2") (pinfunction "2_2") (pintype "passive"))
      (node (ref "U$7") (pin "P$2") (pinfunction "RF_P$2") (pintype "bidirectional"))
    )
    (net (code "106") (name "Net-(U$7-RF1)") (class "Default")
      (node (ref "C38") (pin "1") (pinfunction "1_1") (pintype "passive"))
      (node (ref "U$7") (pin "P$5") (pinfunction "RF1_P$5") (pintype "bidirectional"))
    )
    (net (code "107") (name "Net-(U$7-RF2)") (class "Default")
      (node (ref "C39") (pin "2") (pinfunction "2_2") (pintype "passive"))
      (node (ref "U$7") (pin "P$11") (pinfunction "RF2_P$11") (pintype "bidirectional"))
    )
    (net (code "108") (name "Net-(U$8-2)") (class "Default")
      (node (ref "C64") (pin "2") (pinfunction "2_2") (pintype "passive"))
      (node (ref "U$8") (pin "P$2") (pinfunction "2_P$2") (pintype "bidirectional"))
    )
    (net (code "109") (name "Net-(U$8-5)") (class "Default")
      (node (ref "R37") (pin "2") (pinfunction "2_2") (pintype "passive"))
      (node (ref "R38") (pin "1") (pinfunction "1_1") (pintype "passive"))
      (node (ref "U$8") (pin "P$5") (pinfunction "5_P$5") (pintype "bidirectional"))
    )
    (net (code "110") (name "Net-(U$9-2)") (class "Default")
      (node (ref "C39") (pin "1") (pinfunction "1_1") (pintype "passive"))
      (node (ref "U$9") (pin "P$2") (pinfunction "2_P$2") (pintype "bidirectional"))
    )
    (net (code "111") (name "Net-(U$9-5)") (class "Default")
      (node (ref "M1") (pin "2") (pinfunction "2_2") (pintype "passive"))
      (node (ref "U$9") (pin "P$5") (pinfunction "5_P$5") (pintype "bidirectional"))
    )
    (net (code "112") (name "Net-(U$10-EN)") (class "Default")
      (node (ref "M17") (pin "2") (pinfunction "2_2") (pintype "passive"))
      (node (ref "U$10") (pin "P$6") (pinfunction "EN_P$6") (pintype "bidirectional"))
    )
    (net (code "113") (name "Net-(U$10-RFIN)") (class "Default")
      (node (ref "M3") (pin "2") (pinfunction "2_2") (pintype "passive"))
      (node (ref "M4") (pin "2") (pinfunction "2_2") (pintype "passive"))
      (node (ref "U$10") (pin "P$2") (pinfunction "RFIN_P$2") (pintype "bidirectional"))
    )
    (net (code "114") (name "Net-(U$10-RFOUT)") (class "Default")
      (node (ref "M10") (pin "1") (pinfunction "1_1") (pintype "passive"))
      (node (ref "M11") (pin "2") (pinfunction "2_2") (pintype "passive"))
      (node (ref "M12") (pin "1") (pinfunction "1_1") (pintype "passive"))
      (node (ref "U$10") (pin "P$7") (pinfunction "RFOUT_P$7") (pintype "bidirectional"))
    )
    (net (code "115") (name "Net-(U$10-VBIAS)") (class "Default")
      (node (ref "M4") (pin "1") (pinfunction "1_1") (pintype "passive"))
      (node (ref "M5") (pin "2") (pinfunction "2_2") (pintype "passive"))
      (node (ref "M6") (pin "1") (pinfunction "1_1") (pintype "passive"))
      (node (ref "U$10") (pin "P$3") (pinfunction "VBIAS_P$3") (pintype "bidirectional"))
    )
    (net (code "116") (name "Net-(U1-FB)") (class "Default")
      (node (ref "C36") (pin "2") (pinfunction "2_2") (pintype "passive"))
      (node (ref "R1") (pin "1") (pinfunction "1_1") (pintype "passive"))
      (node (ref "R5") (pin "2") (pinfunction "2_2") (pintype "passive"))
      (node (ref "U1") (pin "4") (pinfunction "FB_4") (pintype "bidirectional"))
    )
    (net (code "117") (name "Net-(U1-SW)") (class "Default")
      (node (ref "L4") (pin "1") (pinfunction "1_1") (pintype "passive"))
      (node (ref "U1") (pin "2") (pinfunction "SW_2") (pintype "bidirectional"))
    )
    (net (code "118") (name "Net-(U3-NR)") (class "Default")
      (node (ref "C25") (pin "1") (pinfunction "1_1") (pintype "passive"))
      (node (ref "U3") (pin "14") (pinfunction "NR_14") (pintype "bidirectional"))
    )
    (net (code "119") (name "Net-(U6-G8)") (class "Default")
      (node (ref "C53") (pin "1") (pinfunction "1_1") (pintype "passive"))
      (node (ref "R36") (pin "1") (pinfunction "1_1") (pintype "passive"))
      (node (ref "U6") (pin "12") (pinfunction "G8_12") (pintype "bidirectional"))
    )
    (net (code "120") (name "Net-(U6-G16)") (class "Default")
      (node (ref "C52") (pin "1") (pinfunction "1_1") (pintype "passive"))
      (node (ref "R29") (pin "1") (pinfunction "1_1") (pintype "passive"))
      (node (ref "U6") (pin "13") (pinfunction "G16_13") (pintype "bidirectional"))
    )
    (net (code "121") (name "Net-(U6-PD)") (class "Default")
      (node (ref "C62") (pin "1") (pinfunction "1_1") (pintype "passive"))
      (node (ref "C63") (pin "1") (pinfunction "1_1") (pintype "passive"))
      (node (ref "R46") (pin "1") (pinfunction "1_1") (pintype "passive"))
      (node (ref "U6") (pin "6") (pinfunction "PD_6") (pintype "bidirectional"))
    )
    (net (code "122") (name "Net-(U6-RFIN)") (class "Default")
      (node (ref "L7") (pin "2") (pinfunction "2_2") (pintype "passive"))
      (node (ref "U6") (pin "3") (pinfunction "RFIN_3") (pintype "bidirectional"))
    )
    (net (code "123") (name "Net-(U6-RFOUT1)") (class "Default")
      (node (ref "L10") (pin "2") (pinfunction "2_2") (pintype "passive"))
      (node (ref "L9") (pin "1") (pinfunction "1_1") (pintype "passive"))
      (node (ref "U6") (pin "10") (pinfunction "RFOUT2_10") (pintype "bidirectional"))
      (node (ref "U6") (pin "9") (pinfunction "RFOUT1_9") (pintype "bidirectional"))
    )
    (net (code "124") (name "Net-(U6-VBIAS)") (class "Default")
      (node (ref "C50") (pin "1") (pinfunction "1_1") (pintype "passive"))
      (node (ref "C51") (pin "1") (pinfunction "1_1") (pintype "passive"))
      (node (ref "R39") (pin "1") (pinfunction "1_1") (pintype "passive"))
      (node (ref "U6") (pin "16") (pinfunction "VBIAS_16") (pintype "bidirectional"))
    )
    (net (code "125") (name "Net-(U6-VCC1)") (class "Default")
      (node (ref "L8") (pin "2") (pinfunction "2_2") (pintype "passive"))
      (node (ref "U6") (pin "14") (pinfunction "VCC1_14") (pintype "bidirectional"))
    )
    (net (code "126") (name "Net-(U13-UNBALANCE)") (class "Default")
      (node (ref "C64") (pin "1") (pinfunction "1_1") (pintype "passive"))
      (node (ref "U13") (pin "P$2") (pinfunction "UNBALANCE_P$2") (pintype "bidirectional"))
    )
    (net (code "127") (name "Net-(X1-3V3A)") (class "Default")
      (node (ref "X1") (pin "1") (pinfunction "3V3A_1") (pintype "power_in"))
      (node (ref "X1") (pin "17") (pinfunction "3V3B_17") (pintype "power_in"))
    )
    (net (code "128") (name "Net-(X1-SPI_CE0)") (class "Default")
      (node (ref "JP1") (pin "3") (pinfunction "3_3") (pintype "passive"))
      (node (ref "X1") (pin "24") (pinfunction "SPI_CE0_24") (pintype "bidirectional"))
    )
    (net (code "129") (name "Net-(X1-SPI_CE1)") (class "Default")
      (node (ref "JP1") (pin "1") (pinfunction "1_1") (pintype "passive"))
      (node (ref "X1") (pin "26") (pinfunction "SPI_CE1_26") (pintype "bidirectional"))
    )
    (net (code "130") (name "Net-(X1-SPI_MISO)") (class "Default")
      (node (ref "R24") (pin "1") (pinfunction "1_1") (pintype "passive"))
      (node (ref "X1") (pin "21") (pinfunction "SPI_MISO_21") (pintype "bidirectional"))
    )
    (net (code "131") (name "Net-(X1-SPI_MOSI)") (class "Default")
      (node (ref "R26") (pin "1") (pinfunction "1_1") (pintype "passive"))
      (node (ref "X1") (pin "19") (pinfunction "SPI_MOSI_19") (pintype "bidirectional"))
    )
    (net (code "132") (name "Net-(X1-SPI_SCLK)") (class "Default")
      (node (ref "R17") (pin "1") (pinfunction "1_1") (pintype "passive"))
      (node (ref "X1") (pin "23") (pinfunction "SPI_SCLK_23") (pintype "bidirectional"))
    )
    (net (code "133") (name "unconnected-(U$1-GPS_IN-Pad9)") (class "Default")
      (node (ref "U$1") (pin "9") (pinfunction "GPS_IN_9") (pintype "bidirectional"))
    )
    (net (code "134") (name "unconnected-(U$1-LNA_B_CTRL-Pad27)") (class "Default")
      (node (ref "U$1") (pin "27") (pinfunction "LNA_B_CTRL_27") (pintype "bidirectional"))
    )
    (net (code "135") (name "unconnected-(U$1-PA_B_CTRL-Pad26)") (class "Default")
      (node (ref "U$1") (pin "26") (pinfunction "PA_B_CTRL_26") (pintype "bidirectional"))
    )
    (net (code "136") (name "unconnected-(U$1-RADIO_B_EN-Pad28)") (class "Default")
      (node (ref "U$1") (pin "28") (pinfunction "RADIO_B_EN_28") (pintype "bidirectional"))
    )
    (net (code "137") (name "unconnected-(U$2-DIO0-Pad21)") (class "Default")
      (node (ref "U$2") (pin "21") (pinfunction "DIO0_21") (pintype "bidirectional"))
    )
    (net (code "138") (name "unconnected-(U$2-DIO1-Pad22)") (class "Default")
      (node (ref "U$2") (pin "22") (pinfunction "DIO1_22") (pintype "bidirectional"))
    )
    (net (code "139") (name "unconnected-(U$2-DIO2-Pad23)") (class "Default")
      (node (ref "U$2") (pin "23") (pinfunction "DIO2_23") (pintype "bidirectional"))
    )
    (net (code "140") (name "unconnected-(U$2-DIO3-Pad24)") (class "Default")
      (node (ref "U$2") (pin "24") (pinfunction "DIO3_24") (pintype "bidirectional"))
    )
    (net (code "141") (name "unconnected-(U$2-XTA-Pad6)") (class "Default")
      (node (ref "U$2") (pin "6") (pinfunction "XTA_6") (pintype "bidirectional"))
    )
    (net (code "142") (name "unconnected-(U$3-CLK_IN-Pad11)") (class "Default")
      (node (ref "U$3") (pin "11") (pinfunction "CLK_IN_11") (pintype "bidirectional"))
    )
    (net (code "143") (name "unconnected-(U$3-DIO0-Pad21)") (class "Default")
      (node (ref "U$3") (pin "21") (pinfunction "DIO0_21") (pintype "bidirectional"))
    )
    (net (code "144") (name "unconnected-(U$3-DIO1-Pad22)") (class "Default")
      (node (ref "U$3") (pin "22") (pinfunction "DIO1_22") (pintype "bidirectional"))
    )
    (net (code "145") (name "unconnected-(U$3-DIO2-Pad23)") (class "Default")
      (node (ref "U$3") (pin "23") (pinfunction "DIO2_23") (pintype "bidirectional"))
    )
    (net (code "146") (name "unconnected-(U$3-DIO3-Pad24)") (class "Default")
      (node (ref "U$3") (pin "24") (pinfunction "DIO3_24") (pintype "bidirectional"))
    )
    (net (code "147") (name "unconnected-(U$3-RF_ON-Pad29)") (class "Default")
      (node (ref "U$3") (pin "29") (pinfunction "RF_ON_29") (pintype "bidirectional"))
    )
    (net (code "148") (name "unconnected-(U$3-RF_OP-Pad30)") (class "Default")
      (node (ref "U$3") (pin "30") (pinfunction "RF_OP_30") (pintype "bidirectional"))
    )
    (net (code "149") (name "unconnected-(U$3-XTA-Pad6)") (class "Default")
      (node (ref "U$3") (pin "6") (pinfunction "XTA_6") (pintype "bidirectional"))
    )
    (net (code "150") (name "unconnected-(U$5-PG-PadP$3)") (class "Default")
      (node (ref "U$5") (pin "P$3") (pinfunction "PG_P$3") (pintype "bidirectional"))
    )
    (net (code "151") (name "unconnected-(U$10-NC-PadP$1)") (class "Default")
      (node (ref "U$10") (pin "P$1") (pinfunction "NC_P$1") (pintype "bidirectional"))
    )
    (net (code "152") (name "unconnected-(U$10-NC2-PadP$4)") (class "Default")
      (node (ref "U$10") (pin "P$4") (pinfunction "NC2_P$4") (pintype "bidirectional"))
    )
    (net (code "153") (name "unconnected-(U$10-NC3-PadP$5)") (class "Default")
      (node (ref "U$10") (pin "P$5") (pinfunction "NC3_P$5") (pintype "bidirectional"))
    )
    (net (code "154") (name "unconnected-(U$10-NC4-PadP$8)") (class "Default")
      (node (ref "U$10") (pin "P$8") (pinfunction "NC4_P$8") (pintype "bidirectional"))
    )
    (net (code "155") (name "unconnected-(U3-0.4-Pad10)") (class "Default")
      (node (ref "U3") (pin "10") (pinfunction "0.4_10") (pintype "bidirectional"))
    )
    (net (code "156") (name "unconnected-(U3-0.8-Pad9)") (class "Default")
      (node (ref "U3") (pin "9") (pinfunction "0.8_9") (pintype "bidirectional"))
    )
    (net (code "157") (name "unconnected-(U3-3.2-Pad6)") (class "Default")
      (node (ref "U3") (pin "6") (pinfunction "3.2_6") (pintype "bidirectional"))
    )
    (net (code "158") (name "unconnected-(U3-6.4A-Pad4)") (class "Default")
      (node (ref "U3") (pin "4") (pinfunction "6.4A_4") (pintype "bidirectional"))
    )
    (net (code "159") (name "unconnected-(U3-6.4B-Pad5)") (class "Default")
      (node (ref "U3") (pin "5") (pinfunction "6.4B_5") (pintype "bidirectional"))
    )
    (net (code "160") (name "unconnected-(X1-GPIO04-Pad7)") (class "Default")
      (node (ref "X1") (pin "7") (pinfunction "GPIO04_7") (pintype "bidirectional"))
    )
    (net (code "161") (name "unconnected-(X1-GPIO05-Pad29)") (class "Default")
      (node (ref "X1") (pin "29") (pinfunction "GPIO05_29") (pintype "no_connect"))
    )
    (net (code "162") (name "unconnected-(X1-GPIO06-Pad31)") (class "Default")
      (node (ref "X1") (pin "31") (pinfunction "GPIO06_31") (pintype "no_connect"))
    )
    (net (code "163") (name "unconnected-(X1-GPIO12-Pad32)") (class "Default")
      (node (ref "X1") (pin "32") (pinfunction "GPIO12_32") (pintype "no_connect"))
    )
    (net (code "164") (name "unconnected-(X1-GPIO13-Pad33)") (class "Default")
      (node (ref "X1") (pin "33") (pinfunction "GPIO13_33") (pintype "no_connect"))
    )
    (net (code "165") (name "unconnected-(X1-GPIO16-Pad36)") (class "Default")
      (node (ref "X1") (pin "36") (pinfunction "GPIO16_36") (pintype "no_connect"))
    )
    (net (code "166") (name "unconnected-(X1-GPIO17-Pad11)") (class "Default")
      (node (ref "X1") (pin "11") (pinfunction "GPIO17_11") (pintype "bidirectional"))
    )
    (net (code "167") (name "unconnected-(X1-GPIO18-Pad12)") (class "Default")
      (node (ref "X1") (pin "12") (pinfunction "GPIO18_12") (pintype "bidirectional"))
    )
    (net (code "168") (name "unconnected-(X1-GPIO19-Pad35)") (class "Default")
      (node (ref "X1") (pin "35") (pinfunction "GPIO19_35") (pintype "no_connect"))
    )
    (net (code "169") (name "unconnected-(X1-GPIO20-Pad38)") (class "Default")
      (node (ref "X1") (pin "38") (pinfunction "GPIO20_38") (pintype "no_connect"))
    )
    (net (code "170") (name "unconnected-(X1-GPIO21-Pad40)") (class "Default")
      (node (ref "X1") (pin "40") (pinfunction "GPIO21_40") (pintype "no_connect"))
    )
    (net (code "171") (name "unconnected-(X1-GPIO22-Pad15)") (class "Default")
      (node (ref "X1") (pin "15") (pinfunction "GPIO22_15") (pintype "bidirectional"))
    )
    (net (code "172") (name "unconnected-(X1-GPIO23-Pad16)") (class "Default")
      (node (ref "X1") (pin "16") (pinfunction "GPIO23_16") (pintype "bidirectional"))
    )
    (net (code "173") (name "unconnected-(X1-GPIO24-Pad18)") (class "Default")
      (node (ref "X1") (pin "18") (pinfunction "GPIO24_18") (pintype "bidirectional"))
    )
    (net (code "174") (name "unconnected-(X1-GPIO26-Pad37)") (class "Default")
      (node (ref "X1") (pin "37") (pinfunction "GPIO26_37") (pintype "no_connect"))
    )
    (net (code "175") (name "unconnected-(X1-GPIO27-Pad13)") (class "Default")
      (node (ref "X1") (pin "13") (pinfunction "GPIO27_13") (pintype "bidirectional"))
    )
    (net (code "176") (name "unconnected-(X1-ID_SC-Pad28)") (class "Default")
      (node (ref "X1") (pin "28") (pinfunction "ID_SC_28") (pintype "no_connect"))
    )
    (net (code "177") (name "unconnected-(X1-ID_SD-Pad27)") (class "Default")
      (node (ref "X1") (pin "27") (pinfunction "ID_SD_27") (pintype "no_connect"))
    )
    (net (code "178") (name "unconnected-(X1-SCL-Pad5)") (class "Default")
      (node (ref "X1") (pin "5") (pinfunction "SCL_5") (pintype "bidirectional"))
    )
    (net (code "179") (name "unconnected-(X1-SDA-Pad3)") (class "Default")
      (node (ref "X1") (pin "3") (pinfunction "SDA_3") (pintype "bidirectional"))
    )
  )
)
